# DNVT_box3r.net
KiCad netlist of a schematic drawn in EAGLE
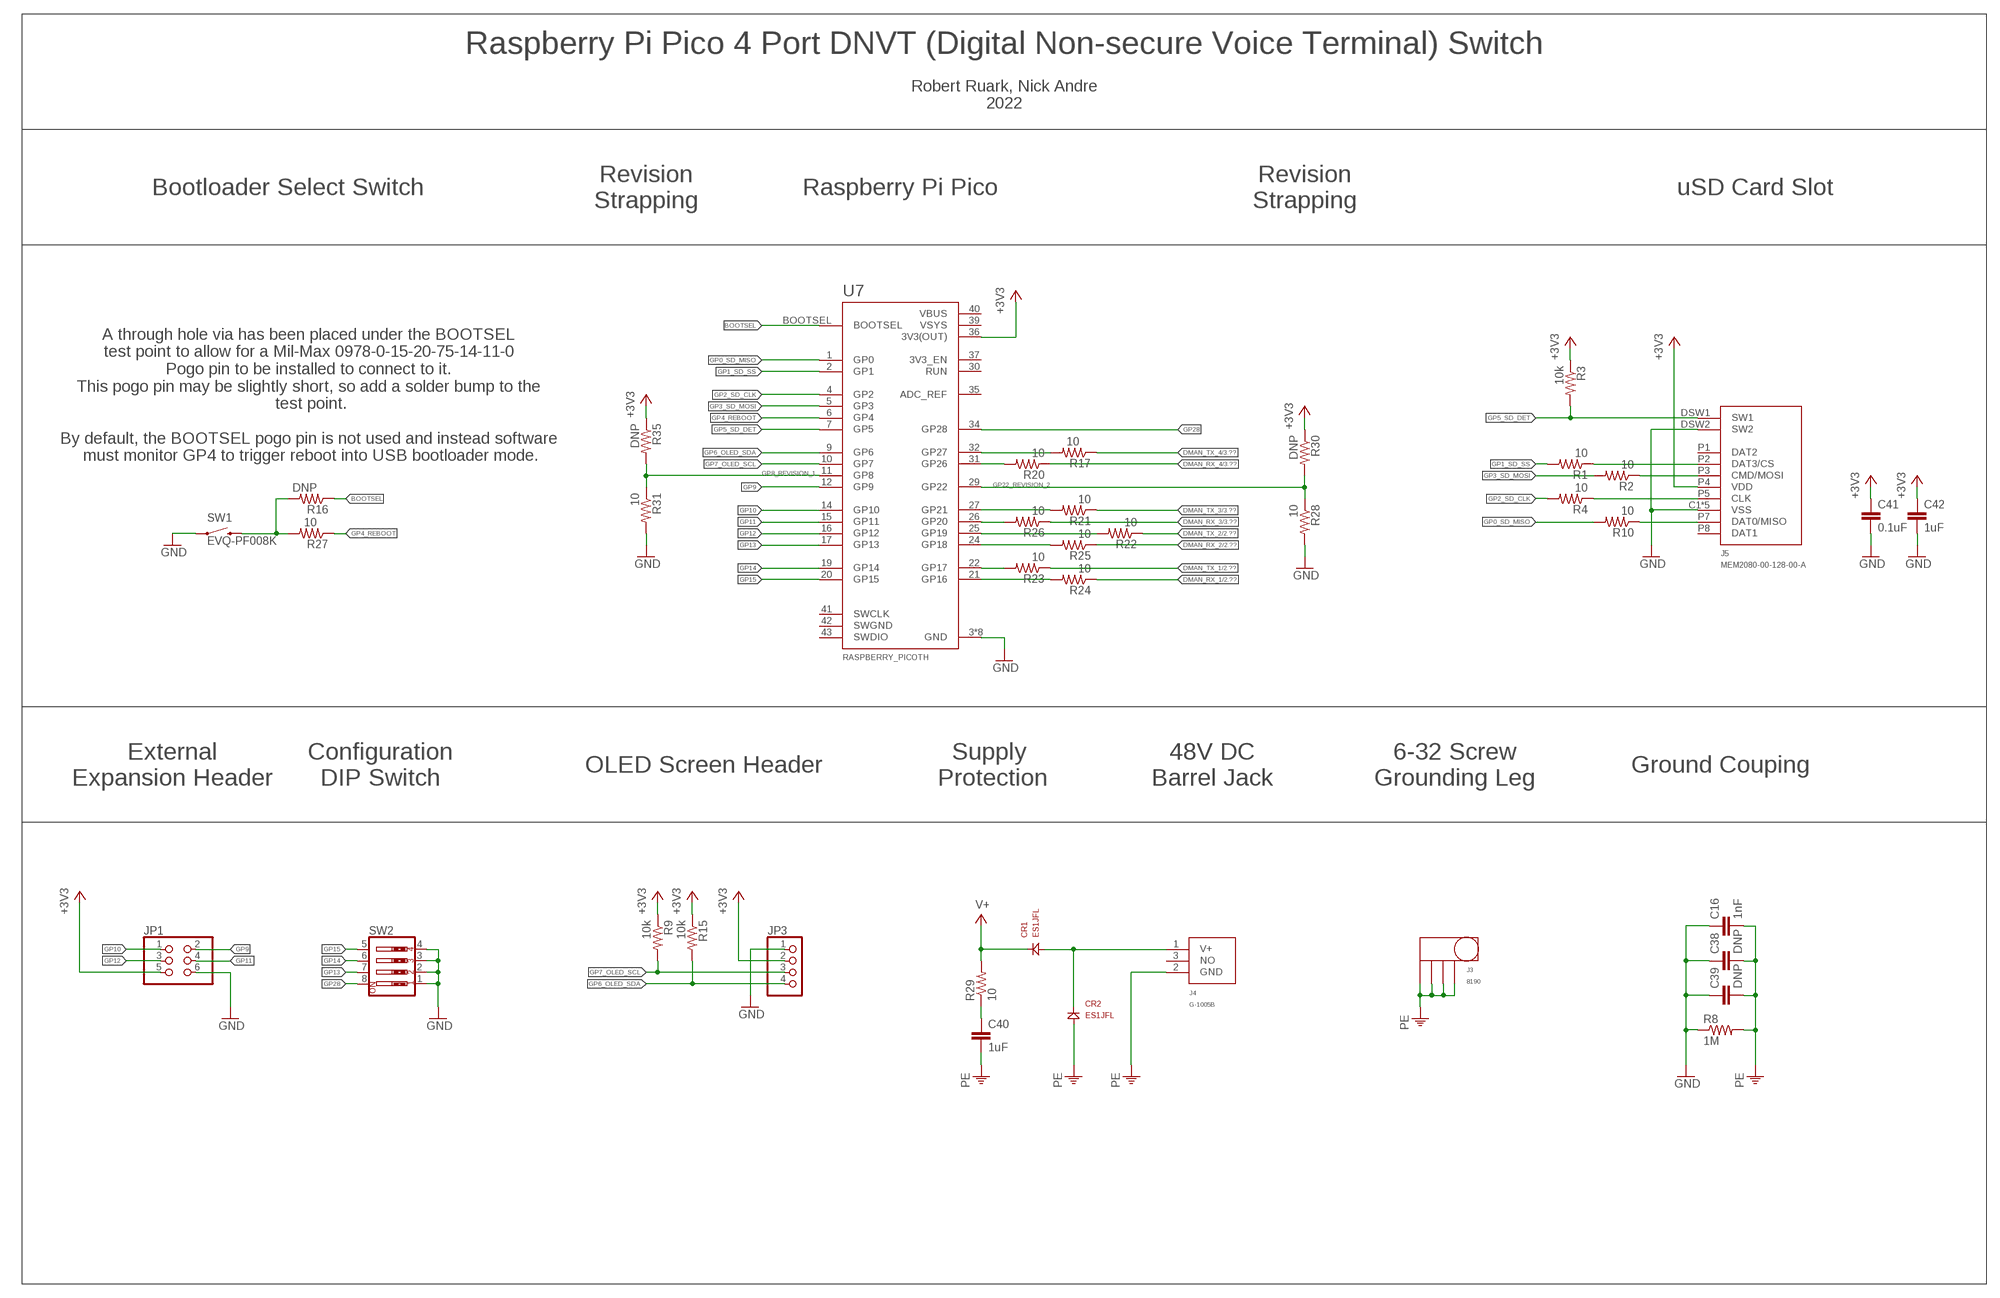
[diagram p0: schematic, sheet 1]
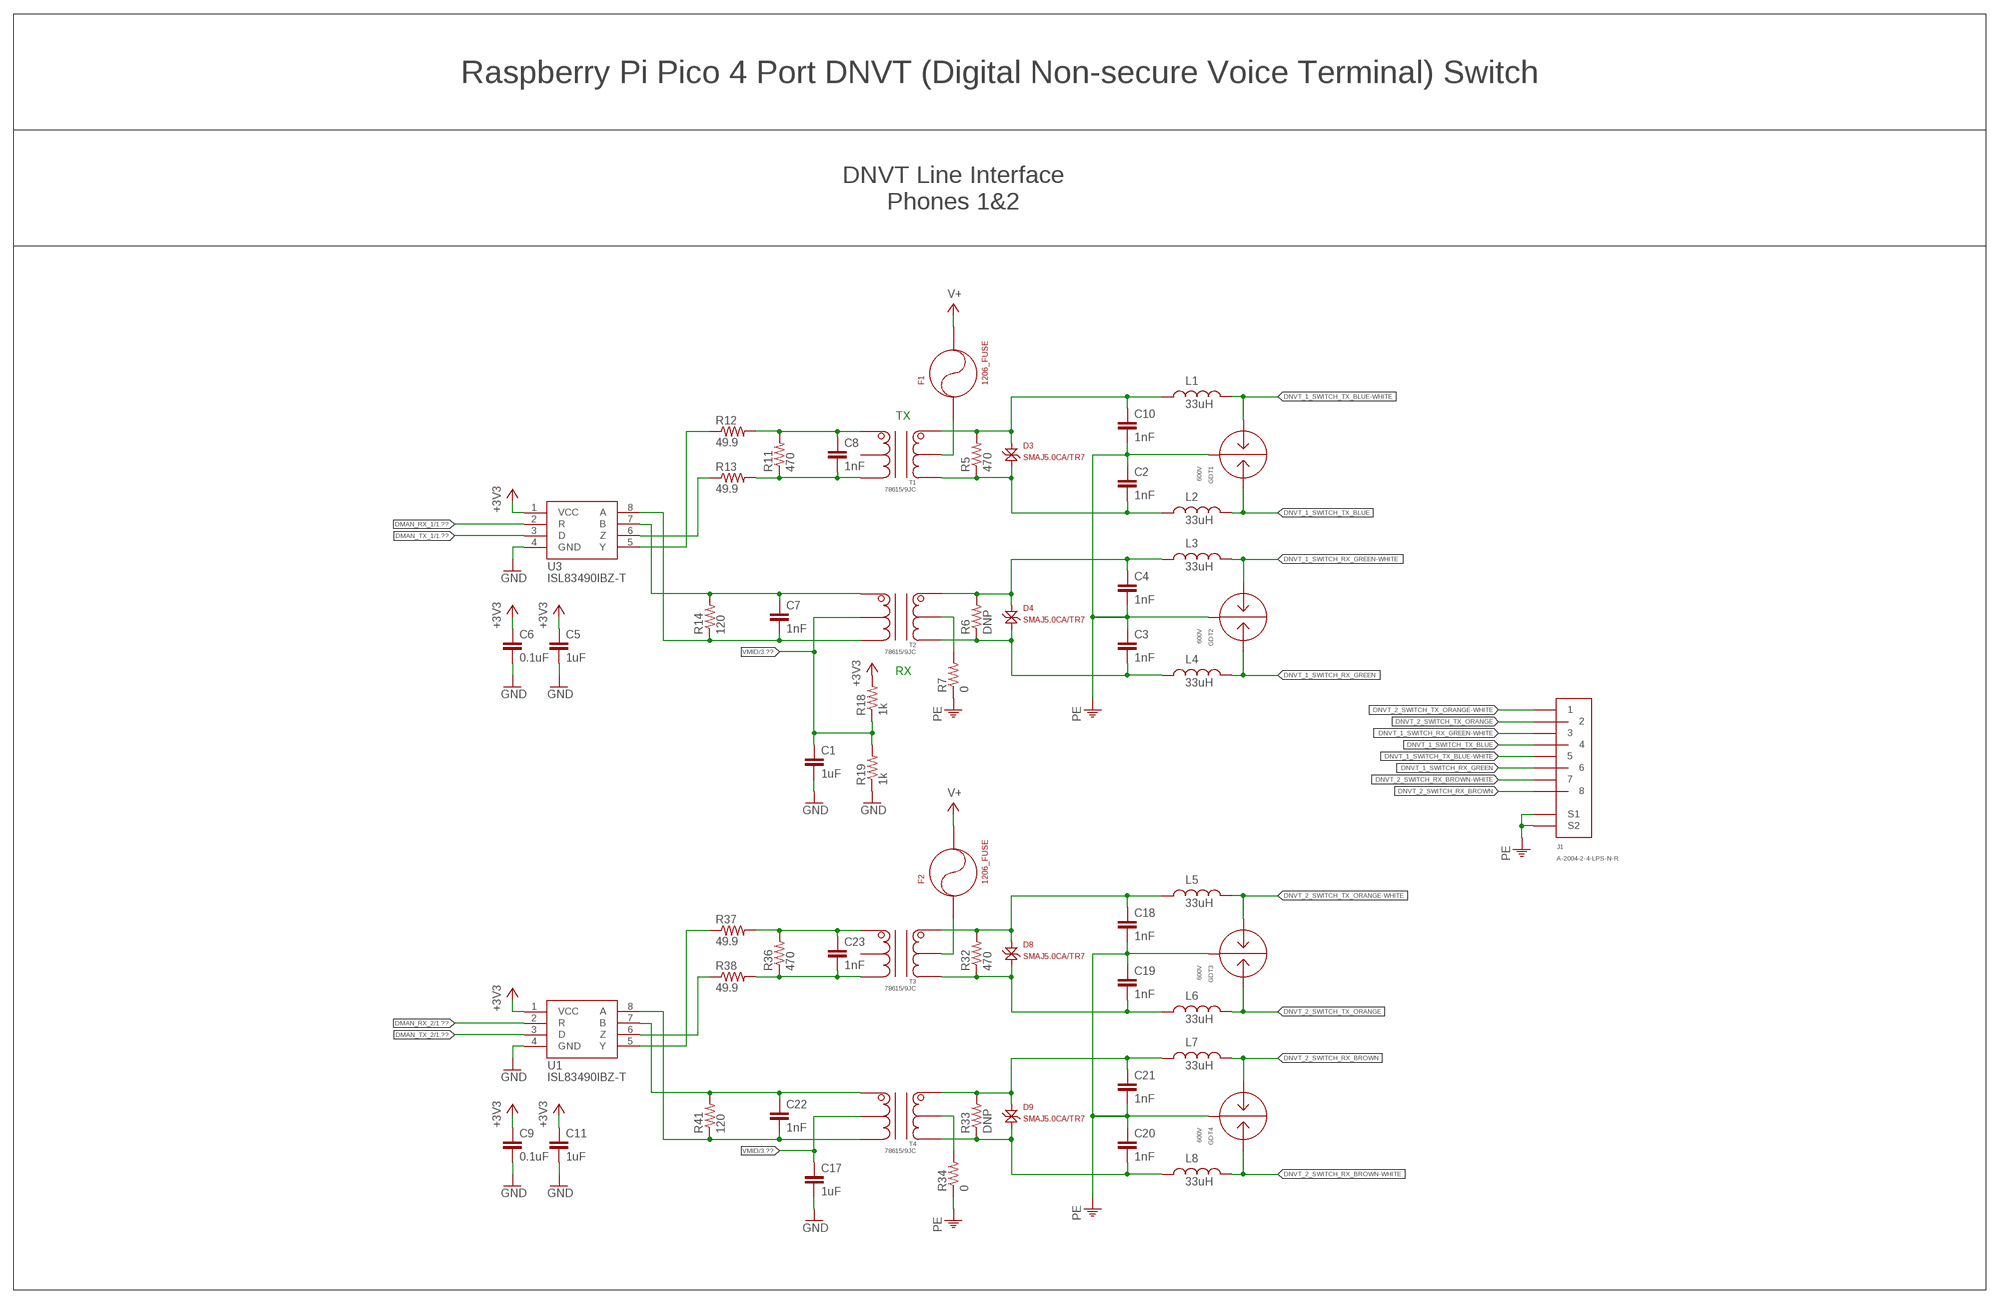
[diagram p1: schematic, sheet 2]
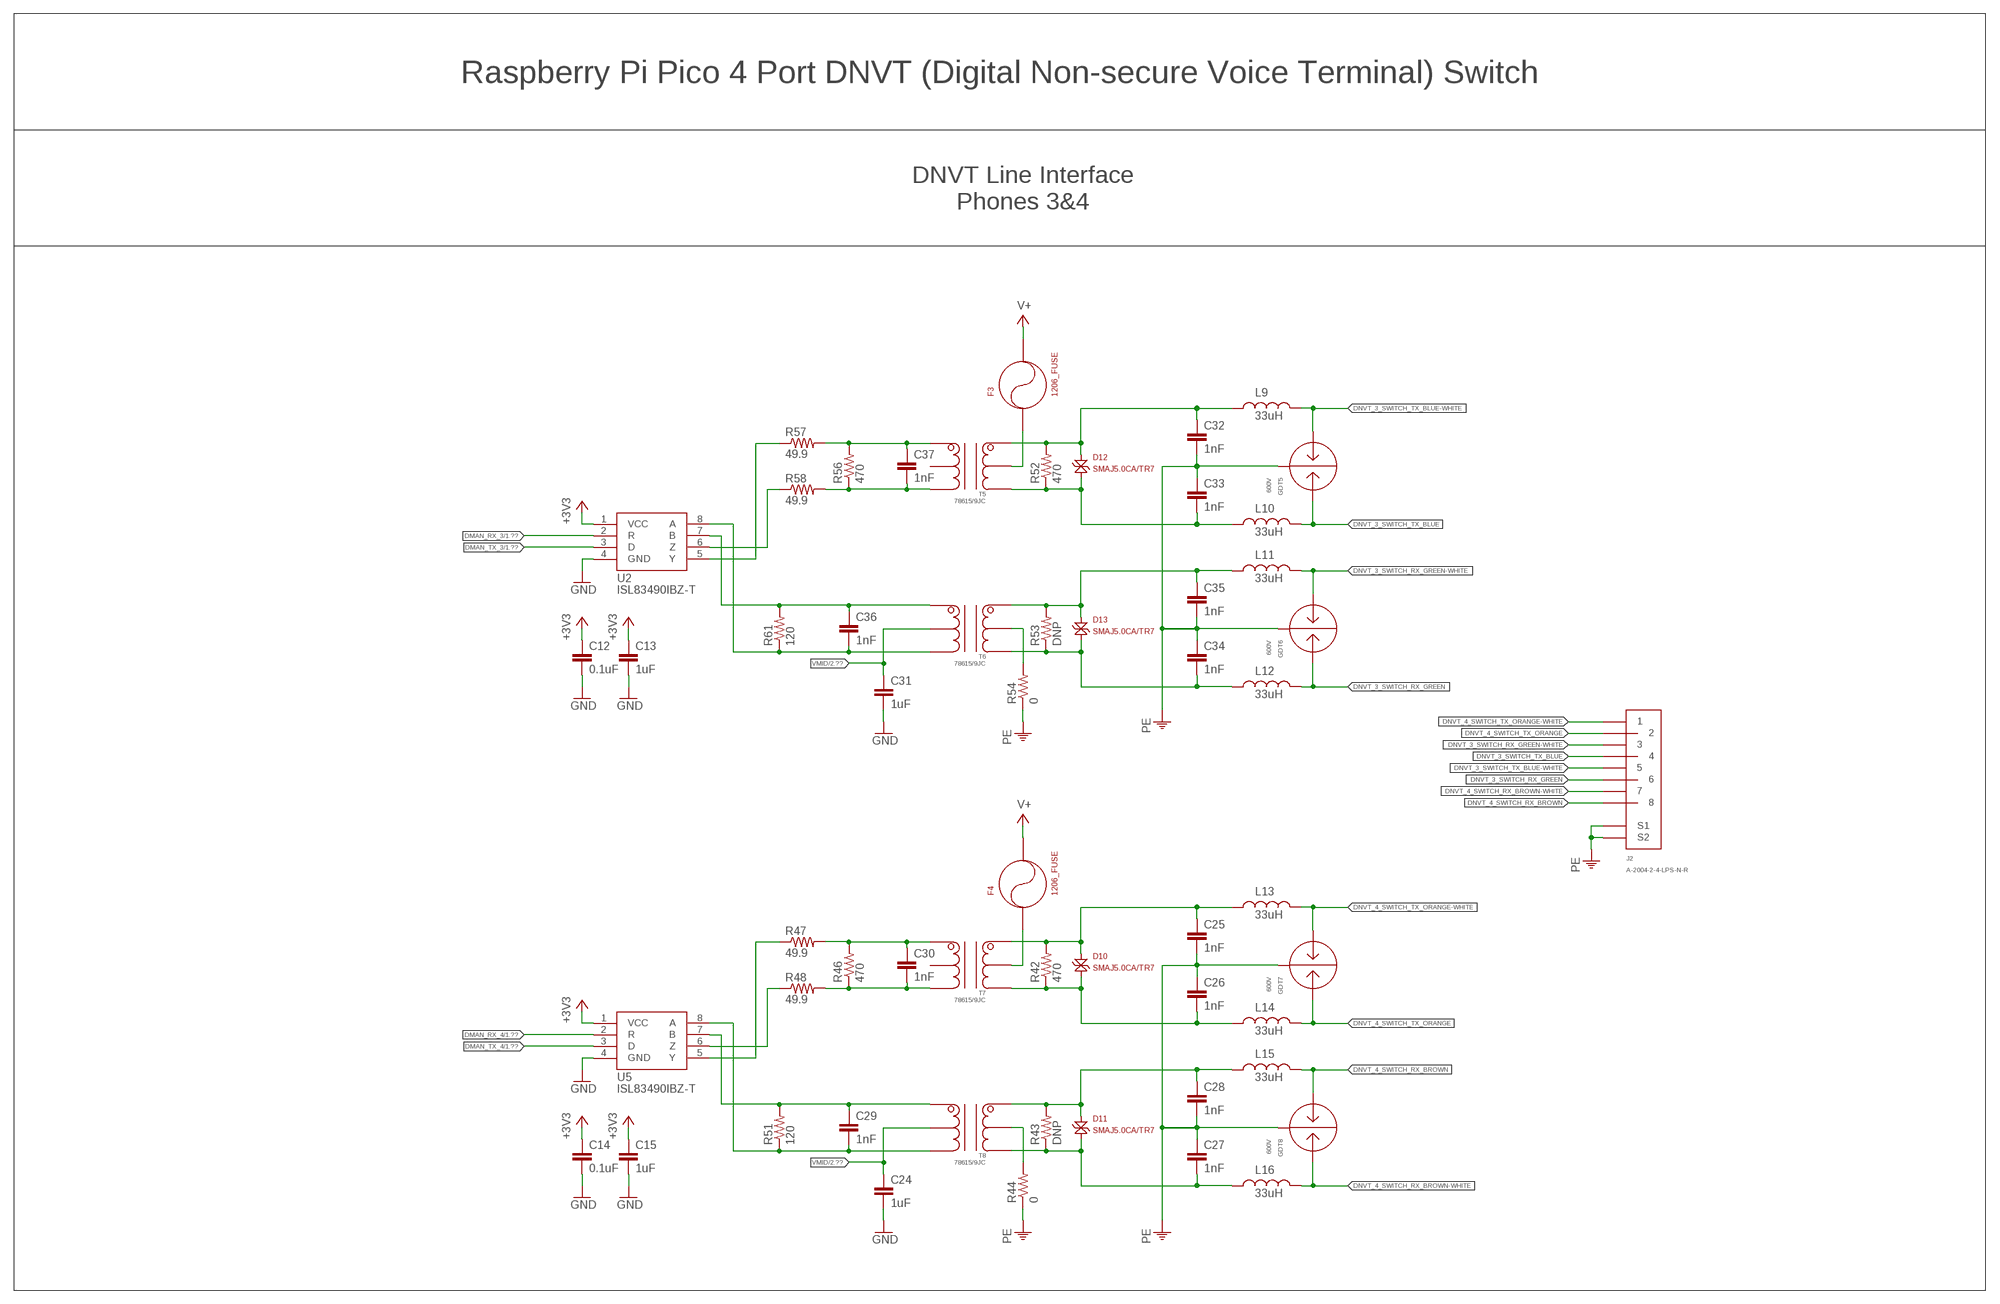
[diagram p2: schematic, sheet 3]

(export (version "E")
  (design (tool "Eeschema 10.0.6"))
  (components
    (comp (ref "C12")
      (value "0.1uF")
      (footprint "eagle-import:0603")
      (libsource (lib "eagle-import") (part "0603_CAPACITOR"))
    )
    (comp (ref "C13")
      (value "1uF")
      (footprint "eagle-import:0805")
      (libsource (lib "eagle-import") (part "0805_CAPACITOR"))
    )
    (comp (ref "C14")
      (value "0.1uF")
      (footprint "eagle-import:0603")
      (libsource (lib "eagle-import") (part "0603_CAPACITOR"))
    )
    (comp (ref "C15")
      (value "1uF")
      (footprint "eagle-import:0805")
      (libsource (lib "eagle-import") (part "0805_CAPACITOR"))
    )
    (comp (ref "C24")
      (value "1uF")
      (footprint "eagle-import:0805")
      (libsource (lib "eagle-import") (part "0805_CAPACITOR"))
    )
    (comp (ref "C25")
      (value "1nF")
      (footprint "eagle-import:0805")
      (libsource (lib "eagle-import") (part "0805_CAPACITOR"))
    )
    (comp (ref "C26")
      (value "1nF")
      (footprint "eagle-import:0805")
      (libsource (lib "eagle-import") (part "0805_CAPACITOR"))
    )
    (comp (ref "C27")
      (value "1nF")
      (footprint "eagle-import:0805")
      (libsource (lib "eagle-import") (part "0805_CAPACITOR"))
    )
    (comp (ref "C28")
      (value "1nF")
      (footprint "eagle-import:0805")
      (libsource (lib "eagle-import") (part "0805_CAPACITOR"))
    )
    (comp (ref "C29")
      (value "1nF")
      (footprint "eagle-import:0805")
      (libsource (lib "eagle-import") (part "0805_CAPACITOR"))
    )
    (comp (ref "C30")
      (value "1nF")
      (footprint "eagle-import:0805")
      (libsource (lib "eagle-import") (part "0805_CAPACITOR"))
    )
    (comp (ref "C31")
      (value "1uF")
      (footprint "eagle-import:0805")
      (libsource (lib "eagle-import") (part "0805_CAPACITOR"))
    )
    (comp (ref "C32")
      (value "1nF")
      (footprint "eagle-import:0805")
      (libsource (lib "eagle-import") (part "0805_CAPACITOR"))
    )
    (comp (ref "C33")
      (value "1nF")
      (footprint "eagle-import:0805")
      (libsource (lib "eagle-import") (part "0805_CAPACITOR"))
    )
    (comp (ref "C34")
      (value "1nF")
      (footprint "eagle-import:0805")
      (libsource (lib "eagle-import") (part "0805_CAPACITOR"))
    )
    (comp (ref "C35")
      (value "1nF")
      (footprint "eagle-import:0805")
      (libsource (lib "eagle-import") (part "0805_CAPACITOR"))
    )
    (comp (ref "C36")
      (value "1nF")
      (footprint "eagle-import:0805")
      (libsource (lib "eagle-import") (part "0805_CAPACITOR"))
    )
    (comp (ref "C37")
      (value "1nF")
      (footprint "eagle-import:0805")
      (libsource (lib "eagle-import") (part "0805_CAPACITOR"))
    )
    (comp (ref "D10")
      (value "SMAJ5.0CA/TR7")
      (footprint "eagle-import:DO-214AC_NO_POL")
      (libsource (lib "eagle-import") (part "SMAJ5.0CA/TR7"))
    )
    (comp (ref "D11")
      (value "SMAJ5.0CA/TR7")
      (footprint "eagle-import:DO-214AC_NO_POL")
      (libsource (lib "eagle-import") (part "SMAJ5.0CA/TR7"))
    )
    (comp (ref "D12")
      (value "SMAJ5.0CA/TR7")
      (footprint "eagle-import:DO-214AC_NO_POL")
      (libsource (lib "eagle-import") (part "SMAJ5.0CA/TR7"))
    )
    (comp (ref "D13")
      (value "SMAJ5.0CA/TR7")
      (footprint "eagle-import:DO-214AC_NO_POL")
      (libsource (lib "eagle-import") (part "SMAJ5.0CA/TR7"))
    )
    (comp (ref "F3")
      (value "1206_FUSE")
      (footprint "eagle-import:1206")
      (libsource (lib "eagle-import") (part "1206_FUSE"))
    )
    (comp (ref "F4")
      (value "1206_FUSE")
      (footprint "eagle-import:1206")
      (libsource (lib "eagle-import") (part "1206_FUSE"))
    )
    (comp (ref "GDT5")
      (value "600V")
      (footprint "eagle-import:2036_GDT")
      (fields (field (name "PARTNO") "2036-60-SM-RPLFCT-ND"))
      (libsource (lib "eagle-import") (part "2036-60-SM-RPLF"))
    )
    (comp (ref "GDT6")
      (value "600V")
      (footprint "eagle-import:2036_GDT")
      (fields (field (name "PARTNO") "2036-60-SM-RPLFCT-ND"))
      (libsource (lib "eagle-import") (part "2036-60-SM-RPLF"))
    )
    (comp (ref "GDT7")
      (value "600V")
      (footprint "eagle-import:2036_GDT")
      (fields (field (name "PARTNO") "2036-60-SM-RPLFCT-ND"))
      (libsource (lib "eagle-import") (part "2036-60-SM-RPLF"))
    )
    (comp (ref "GDT8")
      (value "600V")
      (footprint "eagle-import:2036_GDT")
      (fields (field (name "PARTNO") "2036-60-SM-RPLFCT-ND"))
      (libsource (lib "eagle-import") (part "2036-60-SM-RPLF"))
    )
    (comp (ref "J2")
      (value "A-2004-2-4-LPS-N-R")
      (footprint "eagle-import:A-2004-2-4-LPS-N-R")
      (fields (field (name "PARTNO") "AE10387-ND"))
      (libsource (lib "eagle-import") (part "A-2004-2-4-LPS-N-R"))
    )
    (comp (ref "L9")
      (value "33uH")
      (footprint "eagle-import:SDR0403")
      (fields (field (name "PARTNO") "SDR0403-330KLCT-ND"))
      (libsource (lib "eagle-import") (part "SDR0403-330KL"))
    )
    (comp (ref "L10")
      (value "33uH")
      (footprint "eagle-import:SDR0403")
      (fields (field (name "PARTNO") "SDR0403-330KLCT-ND"))
      (libsource (lib "eagle-import") (part "SDR0403-330KL"))
    )
    (comp (ref "L11")
      (value "33uH")
      (footprint "eagle-import:SDR0403")
      (fields (field (name "PARTNO") "SDR0403-330KLCT-ND"))
      (libsource (lib "eagle-import") (part "SDR0403-330KL"))
    )
    (comp (ref "L12")
      (value "33uH")
      (footprint "eagle-import:SDR0403")
      (fields (field (name "PARTNO") "SDR0403-330KLCT-ND"))
      (libsource (lib "eagle-import") (part "SDR0403-330KL"))
    )
    (comp (ref "L13")
      (value "33uH")
      (footprint "eagle-import:SDR0403")
      (fields (field (name "PARTNO") "SDR0403-330KLCT-ND"))
      (libsource (lib "eagle-import") (part "SDR0403-330KL"))
    )
    (comp (ref "L14")
      (value "33uH")
      (footprint "eagle-import:SDR0403")
      (fields (field (name "PARTNO") "SDR0403-330KLCT-ND"))
      (libsource (lib "eagle-import") (part "SDR0403-330KL"))
    )
    (comp (ref "L15")
      (value "33uH")
      (footprint "eagle-import:SDR0403")
      (fields (field (name "PARTNO") "SDR0403-330KLCT-ND"))
      (libsource (lib "eagle-import") (part "SDR0403-330KL"))
    )
    (comp (ref "L16")
      (value "33uH")
      (footprint "eagle-import:SDR0403")
      (fields (field (name "PARTNO") "SDR0403-330KLCT-ND"))
      (libsource (lib "eagle-import") (part "SDR0403-330KL"))
    )
    (comp (ref "R42")
      (value "470")
      (footprint "eagle-import:R0805")
      (libsource (lib "eagle-import") (part "R-US_R0805"))
    )
    (comp (ref "R43")
      (value "DNP")
      (footprint "eagle-import:R0805")
      (libsource (lib "eagle-import") (part "R-US_R0805"))
    )
    (comp (ref "R44")
      (value "0")
      (footprint "eagle-import:R0805")
      (libsource (lib "eagle-import") (part "R-US_R0805"))
    )
    (comp (ref "R46")
      (value "470")
      (footprint "eagle-import:R0805")
      (libsource (lib "eagle-import") (part "R-US_R0805"))
    )
    (comp (ref "R47")
      (value "49.9")
      (footprint "eagle-import:R0805")
      (libsource (lib "eagle-import") (part "R-US_R0805"))
    )
    (comp (ref "R48")
      (value "49.9")
      (footprint "eagle-import:R0805")
      (libsource (lib "eagle-import") (part "R-US_R0805"))
    )
    (comp (ref "R51")
      (value "120")
      (footprint "eagle-import:1206")
      (libsource (lib "eagle-import") (part "1206_RESISTOR"))
    )
    (comp (ref "R52")
      (value "470")
      (footprint "eagle-import:R0805")
      (libsource (lib "eagle-import") (part "R-US_R0805"))
    )
    (comp (ref "R53")
      (value "DNP")
      (footprint "eagle-import:R0805")
      (libsource (lib "eagle-import") (part "R-US_R0805"))
    )
    (comp (ref "R54")
      (value "0")
      (footprint "eagle-import:R0805")
      (libsource (lib "eagle-import") (part "R-US_R0805"))
    )
    (comp (ref "R56")
      (value "470")
      (footprint "eagle-import:R0805")
      (libsource (lib "eagle-import") (part "R-US_R0805"))
    )
    (comp (ref "R57")
      (value "49.9")
      (footprint "eagle-import:R0805")
      (libsource (lib "eagle-import") (part "R-US_R0805"))
    )
    (comp (ref "R58")
      (value "49.9")
      (footprint "eagle-import:R0805")
      (libsource (lib "eagle-import") (part "R-US_R0805"))
    )
    (comp (ref "R61")
      (value "120")
      (footprint "eagle-import:1206")
      (libsource (lib "eagle-import") (part "1206_RESISTOR"))
    )
    (comp (ref "T5")
      (value "78615/9JC")
      (footprint "eagle-import:786")
      (fields (field (name "PARTNO") "811-2423-ND"))
      (libsource (lib "eagle-import") (part "78615/9JC"))
    )
    (comp (ref "T6")
      (value "78615/9JC")
      (footprint "eagle-import:786")
      (fields (field (name "PARTNO") "811-2423-ND"))
      (libsource (lib "eagle-import") (part "78615/9JC"))
    )
    (comp (ref "T7")
      (value "78615/9JC")
      (footprint "eagle-import:786")
      (fields (field (name "PARTNO") "811-2423-ND"))
      (libsource (lib "eagle-import") (part "78615/9JC"))
    )
    (comp (ref "T8")
      (value "78615/9JC")
      (footprint "eagle-import:786")
      (fields (field (name "PARTNO") "811-2423-ND"))
      (libsource (lib "eagle-import") (part "78615/9JC"))
    )
    (comp (ref "U2")
      (value "ISL83490IBZ-T")
      (footprint "eagle-import:SOIC8")
      (fields (field (name "PARTNO") "ISL83490IBZ-TCT-ND"))
      (libsource (lib "eagle-import") (part "ISL83490IBZ-T"))
    )
    (comp (ref "U5")
      (value "ISL83490IBZ-T")
      (footprint "eagle-import:SOIC8")
      (fields (field (name "PARTNO") "ISL83490IBZ-TCT-ND"))
      (libsource (lib "eagle-import") (part "ISL83490IBZ-T"))
    )
    (comp (ref "C16")
      (value "1nF")
      (footprint "eagle-import:1206")
      (libsource (lib "eagle-import") (part "1206_CAPACITOR"))
    )
    (comp (ref "C38")
      (value "DNP")
      (footprint "eagle-import:1206")
      (libsource (lib "eagle-import") (part "1206_CAPACITOR"))
    )
    (comp (ref "C39")
      (value "DNP")
      (footprint "eagle-import:1206")
      (libsource (lib "eagle-import") (part "1206_CAPACITOR"))
    )
    (comp (ref "C40")
      (value "1uF")
      (footprint "eagle-import:1206")
      (libsource (lib "eagle-import") (part "1206_CAPACITOR"))
    )
    (comp (ref "C41")
      (value "0.1uF")
      (footprint "eagle-import:0603")
      (libsource (lib "eagle-import") (part "0603_CAPACITOR"))
    )
    (comp (ref "C42")
      (value "1uF")
      (footprint "eagle-import:0805")
      (libsource (lib "eagle-import") (part "0805_CAPACITOR"))
    )
    (comp (ref "CR1")
      (value "ES1JFL")
      (footprint "eagle-import:SOD123(AK)")
      (fields (field (name "PARTNO") "ES1JFLCT-ND"))
      (libsource (lib "eagle-import") (part "ES1JFL"))
    )
    (comp (ref "CR2")
      (value "ES1JFL")
      (footprint "eagle-import:SOD123(AK)")
      (fields (field (name "PARTNO") "ES1JFLCT-ND"))
      (libsource (lib "eagle-import") (part "ES1JFL"))
    )
    (comp (ref "J3")
      (value "8190")
      (footprint "eagle-import:7781")
      (fields (field (name "PARTNO") "36-8190-ND"))
      (libsource (lib "eagle-import") (part "8190"))
    )
    (comp (ref "J4")
      (value "G-1005B")
      (footprint "eagle-import:G-1005B")
      (fields (field (name "PARTNO") "1939-G-1005B-ND"))
      (libsource (lib "eagle-import") (part "G-1005B"))
    )
    (comp (ref "J5")
      (value "MEM2080-00-128-00-A")
      (footprint "eagle-import:MEM2080")
      (fields (field (name "PARTNO") "2073-MEM2080-00-128-00-ACT-ND"))
      (libsource (lib "eagle-import") (part "MEM2080-00-128-00-A"))
    )
    (comp (ref "JP1")
      (value "PINHD-2X3/90")
      (footprint "eagle-import:2X03_90")
      (libsource (lib "eagle-import") (part "PINHD-2X3/90"))
    )
    (comp (ref "JP3")
      (value "PINHD-1X4")
      (footprint "eagle-import:1X04")
      (libsource (lib "eagle-import") (part "PINHD-1X4"))
    )
    (comp (ref "R1")
      (value "10")
      (footprint "eagle-import:0603")
      (libsource (lib "eagle-import") (part "0603_RESISTOR"))
    )
    (comp (ref "R2")
      (value "10")
      (footprint "eagle-import:0603")
      (libsource (lib "eagle-import") (part "0603_RESISTOR"))
    )
    (comp (ref "R3")
      (value "10k")
      (footprint "eagle-import:0603")
      (libsource (lib "eagle-import") (part "0603_RESISTOR"))
    )
    (comp (ref "R4")
      (value "10")
      (footprint "eagle-import:0603")
      (libsource (lib "eagle-import") (part "0603_RESISTOR"))
    )
    (comp (ref "R8")
      (value "1M")
      (footprint "eagle-import:1206")
      (libsource (lib "eagle-import") (part "1206_RESISTOR"))
    )
    (comp (ref "R9")
      (value "10k")
      (footprint "eagle-import:0603")
      (libsource (lib "eagle-import") (part "0603_RESISTOR"))
    )
    (comp (ref "R10")
      (value "10")
      (footprint "eagle-import:0603")
      (libsource (lib "eagle-import") (part "0603_RESISTOR"))
    )
    (comp (ref "R15")
      (value "10k")
      (footprint "eagle-import:0603")
      (libsource (lib "eagle-import") (part "0603_RESISTOR"))
    )
    (comp (ref "R16")
      (value "DNP")
      (footprint "eagle-import:0603")
      (libsource (lib "eagle-import") (part "0603_RESISTOR"))
    )
    (comp (ref "R17")
      (value "10")
      (footprint "eagle-import:0603")
      (libsource (lib "eagle-import") (part "0603_RESISTOR"))
    )
    (comp (ref "R20")
      (value "10")
      (footprint "eagle-import:0603")
      (libsource (lib "eagle-import") (part "0603_RESISTOR"))
    )
    (comp (ref "R21")
      (value "10")
      (footprint "eagle-import:0603")
      (libsource (lib "eagle-import") (part "0603_RESISTOR"))
    )
    (comp (ref "R22")
      (value "10")
      (footprint "eagle-import:0603")
      (libsource (lib "eagle-import") (part "0603_RESISTOR"))
    )
    (comp (ref "R23")
      (value "10")
      (footprint "eagle-import:0603")
      (libsource (lib "eagle-import") (part "0603_RESISTOR"))
    )
    (comp (ref "R24")
      (value "10")
      (footprint "eagle-import:0603")
      (libsource (lib "eagle-import") (part "0603_RESISTOR"))
    )
    (comp (ref "R25")
      (value "10")
      (footprint "eagle-import:0603")
      (libsource (lib "eagle-import") (part "0603_RESISTOR"))
    )
    (comp (ref "R26")
      (value "10")
      (footprint "eagle-import:0603")
      (libsource (lib "eagle-import") (part "0603_RESISTOR"))
    )
    (comp (ref "R27")
      (value "10")
      (footprint "eagle-import:0603")
      (libsource (lib "eagle-import") (part "0603_RESISTOR"))
    )
    (comp (ref "R28")
      (value "10")
      (footprint "eagle-import:0603")
      (libsource (lib "eagle-import") (part "0603_RESISTOR"))
    )
    (comp (ref "R29")
      (value "10")
      (footprint "eagle-import:1206")
      (libsource (lib "eagle-import") (part "1206_RESISTOR"))
    )
    (comp (ref "R30")
      (value "DNP")
      (footprint "eagle-import:0603")
      (libsource (lib "eagle-import") (part "0603_RESISTOR"))
    )
    (comp (ref "R31")
      (value "10")
      (footprint "eagle-import:0603")
      (libsource (lib "eagle-import") (part "0603_RESISTOR"))
    )
    (comp (ref "R35")
      (value "DNP")
      (footprint "eagle-import:0603")
      (libsource (lib "eagle-import") (part "0603_RESISTOR"))
    )
    (comp (ref "SW1")
      (value "EVQ-PF008K")
      (footprint "eagle-import:EVQ-PF008K")
      (fields (field (name "PARTNO") "P10880S-ND"))
      (libsource (lib "eagle-import") (part "EVQ-PF008K"))
    )
    (comp (ref "SW2")
      (value "SW_DIP-4")
      (footprint "eagle-import:EDG-04")
      (libsource (lib "eagle-import") (part "SW_DIP-4"))
    )
    (comp (ref "U7")
      (value "RASPBERRY_PICOTH")
      (footprint "eagle-import:PICO-PKG-TH")
      (libsource (lib "eagle-import") (part "RASPBERRY_PICOTH"))
    )
    (comp (ref "C1")
      (value "1uF")
      (footprint "eagle-import:0805")
      (libsource (lib "eagle-import") (part "0805_CAPACITOR"))
    )
    (comp (ref "C2")
      (value "1nF")
      (footprint "eagle-import:0805")
      (libsource (lib "eagle-import") (part "0805_CAPACITOR"))
    )
    (comp (ref "C3")
      (value "1nF")
      (footprint "eagle-import:0805")
      (libsource (lib "eagle-import") (part "0805_CAPACITOR"))
    )
    (comp (ref "C4")
      (value "1nF")
      (footprint "eagle-import:0805")
      (libsource (lib "eagle-import") (part "0805_CAPACITOR"))
    )
    (comp (ref "C5")
      (value "1uF")
      (footprint "eagle-import:0805")
      (libsource (lib "eagle-import") (part "0805_CAPACITOR"))
    )
    (comp (ref "C6")
      (value "0.1uF")
      (footprint "eagle-import:0603")
      (libsource (lib "eagle-import") (part "0603_CAPACITOR"))
    )
    (comp (ref "C7")
      (value "1nF")
      (footprint "eagle-import:0805")
      (libsource (lib "eagle-import") (part "0805_CAPACITOR"))
    )
    (comp (ref "C8")
      (value "1nF")
      (footprint "eagle-import:0805")
      (libsource (lib "eagle-import") (part "0805_CAPACITOR"))
    )
    (comp (ref "C9")
      (value "0.1uF")
      (footprint "eagle-import:0603")
      (libsource (lib "eagle-import") (part "0603_CAPACITOR"))
    )
    (comp (ref "C10")
      (value "1nF")
      (footprint "eagle-import:0805")
      (libsource (lib "eagle-import") (part "0805_CAPACITOR"))
    )
    (comp (ref "C11")
      (value "1uF")
      (footprint "eagle-import:0805")
      (libsource (lib "eagle-import") (part "0805_CAPACITOR"))
    )
    (comp (ref "C17")
      (value "1uF")
      (footprint "eagle-import:0805")
      (libsource (lib "eagle-import") (part "0805_CAPACITOR"))
    )
    (comp (ref "C18")
      (value "1nF")
      (footprint "eagle-import:0805")
      (libsource (lib "eagle-import") (part "0805_CAPACITOR"))
    )
    (comp (ref "C19")
      (value "1nF")
      (footprint "eagle-import:0805")
      (libsource (lib "eagle-import") (part "0805_CAPACITOR"))
    )
    (comp (ref "C20")
      (value "1nF")
      (footprint "eagle-import:0805")
      (libsource (lib "eagle-import") (part "0805_CAPACITOR"))
    )
    (comp (ref "C21")
      (value "1nF")
      (footprint "eagle-import:0805")
      (libsource (lib "eagle-import") (part "0805_CAPACITOR"))
    )
    (comp (ref "C22")
      (value "1nF")
      (footprint "eagle-import:0805")
      (libsource (lib "eagle-import") (part "0805_CAPACITOR"))
    )
    (comp (ref "C23")
      (value "1nF")
      (footprint "eagle-import:0805")
      (libsource (lib "eagle-import") (part "0805_CAPACITOR"))
    )
    (comp (ref "D3")
      (value "SMAJ5.0CA/TR7")
      (footprint "eagle-import:DO-214AC_NO_POL")
      (libsource (lib "eagle-import") (part "SMAJ5.0CA/TR7"))
    )
    (comp (ref "D4")
      (value "SMAJ5.0CA/TR7")
      (footprint "eagle-import:DO-214AC_NO_POL")
      (libsource (lib "eagle-import") (part "SMAJ5.0CA/TR7"))
    )
    (comp (ref "D8")
      (value "SMAJ5.0CA/TR7")
      (footprint "eagle-import:DO-214AC_NO_POL")
      (libsource (lib "eagle-import") (part "SMAJ5.0CA/TR7"))
    )
    (comp (ref "D9")
      (value "SMAJ5.0CA/TR7")
      (footprint "eagle-import:DO-214AC_NO_POL")
      (libsource (lib "eagle-import") (part "SMAJ5.0CA/TR7"))
    )
    (comp (ref "F1")
      (value "1206_FUSE")
      (footprint "eagle-import:1206")
      (libsource (lib "eagle-import") (part "1206_FUSE"))
    )
    (comp (ref "F2")
      (value "1206_FUSE")
      (footprint "eagle-import:1206")
      (libsource (lib "eagle-import") (part "1206_FUSE"))
    )
    (comp (ref "GDT1")
      (value "600V")
      (footprint "eagle-import:2036_GDT")
      (fields (field (name "PARTNO") "2036-60-SM-RPLFCT-ND"))
      (libsource (lib "eagle-import") (part "2036-60-SM-RPLF"))
    )
    (comp (ref "GDT2")
      (value "600V")
      (footprint "eagle-import:2036_GDT")
      (fields (field (name "PARTNO") "2036-60-SM-RPLFCT-ND"))
      (libsource (lib "eagle-import") (part "2036-60-SM-RPLF"))
    )
    (comp (ref "GDT3")
      (value "600V")
      (footprint "eagle-import:2036_GDT")
      (fields (field (name "PARTNO") "2036-60-SM-RPLFCT-ND"))
      (libsource (lib "eagle-import") (part "2036-60-SM-RPLF"))
    )
    (comp (ref "GDT4")
      (value "600V")
      (footprint "eagle-import:2036_GDT")
      (fields (field (name "PARTNO") "2036-60-SM-RPLFCT-ND"))
      (libsource (lib "eagle-import") (part "2036-60-SM-RPLF"))
    )
    (comp (ref "J1")
      (value "A-2004-2-4-LPS-N-R")
      (footprint "eagle-import:A-2004-2-4-LPS-N-R")
      (fields (field (name "PARTNO") "AE10387-ND"))
      (libsource (lib "eagle-import") (part "A-2004-2-4-LPS-N-R"))
    )
    (comp (ref "L1")
      (value "33uH")
      (footprint "eagle-import:SDR0403")
      (fields (field (name "PARTNO") "SDR0403-330KLCT-ND"))
      (libsource (lib "eagle-import") (part "SDR0403-330KL"))
    )
    (comp (ref "L2")
      (value "33uH")
      (footprint "eagle-import:SDR0403")
      (fields (field (name "PARTNO") "SDR0403-330KLCT-ND"))
      (libsource (lib "eagle-import") (part "SDR0403-330KL"))
    )
    (comp (ref "L3")
      (value "33uH")
      (footprint "eagle-import:SDR0403")
      (fields (field (name "PARTNO") "SDR0403-330KLCT-ND"))
      (libsource (lib "eagle-import") (part "SDR0403-330KL"))
    )
    (comp (ref "L4")
      (value "33uH")
      (footprint "eagle-import:SDR0403")
      (fields (field (name "PARTNO") "SDR0403-330KLCT-ND"))
      (libsource (lib "eagle-import") (part "SDR0403-330KL"))
    )
    (comp (ref "L5")
      (value "33uH")
      (footprint "eagle-import:SDR0403")
      (fields (field (name "PARTNO") "SDR0403-330KLCT-ND"))
      (libsource (lib "eagle-import") (part "SDR0403-330KL"))
    )
    (comp (ref "L6")
      (value "33uH")
      (footprint "eagle-import:SDR0403")
      (fields (field (name "PARTNO") "SDR0403-330KLCT-ND"))
      (libsource (lib "eagle-import") (part "SDR0403-330KL"))
    )
    (comp (ref "L7")
      (value "33uH")
      (footprint "eagle-import:SDR0403")
      (fields (field (name "PARTNO") "SDR0403-330KLCT-ND"))
      (libsource (lib "eagle-import") (part "SDR0403-330KL"))
    )
    (comp (ref "L8")
      (value "33uH")
      (footprint "eagle-import:SDR0403")
      (fields (field (name "PARTNO") "SDR0403-330KLCT-ND"))
      (libsource (lib "eagle-import") (part "SDR0403-330KL"))
    )
    (comp (ref "R5")
      (value "470")
      (footprint "eagle-import:R0805")
      (libsource (lib "eagle-import") (part "R-US_R0805"))
    )
    (comp (ref "R6")
      (value "DNP")
      (footprint "eagle-import:R0805")
      (libsource (lib "eagle-import") (part "R-US_R0805"))
    )
    (comp (ref "R7")
      (value "0")
      (footprint "eagle-import:R0805")
      (libsource (lib "eagle-import") (part "R-US_R0805"))
    )
    (comp (ref "R11")
      (value "470")
      (footprint "eagle-import:R0805")
      (libsource (lib "eagle-import") (part "R-US_R0805"))
    )
    (comp (ref "R12")
      (value "49.9")
      (footprint "eagle-import:R0805")
      (libsource (lib "eagle-import") (part "R-US_R0805"))
    )
    (comp (ref "R13")
      (value "49.9")
      (footprint "eagle-import:R0805")
      (libsource (lib "eagle-import") (part "R-US_R0805"))
    )
    (comp (ref "R14")
      (value "120")
      (footprint "eagle-import:1206")
      (libsource (lib "eagle-import") (part "1206_RESISTOR"))
    )
    (comp (ref "R18")
      (value "1k")
      (footprint "eagle-import:0603")
      (libsource (lib "eagle-import") (part "0603_RESISTOR"))
    )
    (comp (ref "R19")
      (value "1k")
      (footprint "eagle-import:0603")
      (libsource (lib "eagle-import") (part "0603_RESISTOR"))
    )
    (comp (ref "R32")
      (value "470")
      (footprint "eagle-import:R0805")
      (libsource (lib "eagle-import") (part "R-US_R0805"))
    )
    (comp (ref "R33")
      (value "DNP")
      (footprint "eagle-import:R0805")
      (libsource (lib "eagle-import") (part "R-US_R0805"))
    )
    (comp (ref "R34")
      (value "0")
      (footprint "eagle-import:R0805")
      (libsource (lib "eagle-import") (part "R-US_R0805"))
    )
    (comp (ref "R36")
      (value "470")
      (footprint "eagle-import:R0805")
      (libsource (lib "eagle-import") (part "R-US_R0805"))
    )
    (comp (ref "R37")
      (value "49.9")
      (footprint "eagle-import:R0805")
      (libsource (lib "eagle-import") (part "R-US_R0805"))
    )
    (comp (ref "R38")
      (value "49.9")
      (footprint "eagle-import:R0805")
      (libsource (lib "eagle-import") (part "R-US_R0805"))
    )
    (comp (ref "R41")
      (value "120")
      (footprint "eagle-import:1206")
      (libsource (lib "eagle-import") (part "1206_RESISTOR"))
    )
    (comp (ref "T1")
      (value "78615/9JC")
      (footprint "eagle-import:786")
      (fields (field (name "PARTNO") "811-2423-ND"))
      (libsource (lib "eagle-import") (part "78615/9JC"))
    )
    (comp (ref "T2")
      (value "78615/9JC")
      (footprint "eagle-import:786")
      (fields (field (name "PARTNO") "811-2423-ND"))
      (libsource (lib "eagle-import") (part "78615/9JC"))
    )
    (comp (ref "T3")
      (value "78615/9JC")
      (footprint "eagle-import:786")
      (fields (field (name "PARTNO") "811-2423-ND"))
      (libsource (lib "eagle-import") (part "78615/9JC"))
    )
    (comp (ref "T4")
      (value "78615/9JC")
      (footprint "eagle-import:786")
      (fields (field (name "PARTNO") "811-2423-ND"))
      (libsource (lib "eagle-import") (part "78615/9JC"))
    )
    (comp (ref "U1")
      (value "ISL83490IBZ-T")
      (footprint "eagle-import:SOIC8")
      (fields (field (name "PARTNO") "ISL83490IBZ-TCT-ND"))
      (libsource (lib "eagle-import") (part "ISL83490IBZ-T"))
    )
    (comp (ref "U3")
      (value "ISL83490IBZ-T")
      (footprint "eagle-import:SOIC8")
      (fields (field (name "PARTNO") "ISL83490IBZ-TCT-ND"))
      (libsource (lib "eagle-import") (part "ISL83490IBZ-T"))
    )
  )
  (nets
    (net (code "1") (name "+3V3") (class "Default")
      (node (ref "C11") (pin "1") (pinfunction "1_1") (pintype "passive"))
      (node (ref "C12") (pin "1") (pinfunction "1_1") (pintype "passive"))
      (node (ref "C13") (pin "1") (pinfunction "1_1") (pintype "passive"))
      (node (ref "C14") (pin "1") (pinfunction "1_1") (pintype "passive"))
      (node (ref "C15") (pin "1") (pinfunction "1_1") (pintype "passive"))
      (node (ref "C41") (pin "1") (pinfunction "1_1") (pintype "passive"))
      (node (ref "C42") (pin "1") (pinfunction "1_1") (pintype "passive"))
      (node (ref "C5") (pin "1") (pinfunction "1_1") (pintype "passive"))
      (node (ref "C6") (pin "1") (pinfunction "1_1") (pintype "passive"))
      (node (ref "C9") (pin "1") (pinfunction "1_1") (pintype "passive"))
      (node (ref "J5") (pin "P4") (pinfunction "VDD_P4") (pintype "bidirectional"))
      (node (ref "JP1") (pin "5") (pinfunction "5_5") (pintype "passive"))
      (node (ref "JP3") (pin "2") (pinfunction "2_2") (pintype "passive"))
      (node (ref "R15") (pin "1") (pinfunction "1_1") (pintype "passive"))
      (node (ref "R18") (pin "2") (pinfunction "2_2") (pintype "passive"))
      (node (ref "R3") (pin "1") (pinfunction "1_1") (pintype "passive"))
      (node (ref "R30") (pin "1") (pinfunction "1_1") (pintype "passive"))
      (node (ref "R35") (pin "1") (pinfunction "1_1") (pintype "passive"))
      (node (ref "R9") (pin "1") (pinfunction "1_1") (pintype "passive"))
      (node (ref "U1") (pin "1") (pinfunction "VCC_1") (pintype "bidirectional"))
      (node (ref "U2") (pin "1") (pinfunction "VCC_1") (pintype "bidirectional"))
      (node (ref "U3") (pin "1") (pinfunction "VCC_1") (pintype "bidirectional"))
      (node (ref "U5") (pin "1") (pinfunction "VCC_1") (pintype "bidirectional"))
      (node (ref "U7") (pin "36") (pinfunction "3V3(OUT)_36") (pintype "power_in"))
    )
    (net (code "2") (name "BOOTSEL") (class "Default")
      (node (ref "R16") (pin "1") (pinfunction "1_1") (pintype "passive"))
      (node (ref "U7") (pin "BOOTSEL") (pinfunction "BOOTSEL_BOOTSEL") (pintype "bidirectional"))
    )
    (net (code "3") (name "DMAN_RX_1") (class "Default")
      (node (ref "R24") (pin "1") (pinfunction "1_1") (pintype "passive"))
      (node (ref "U3") (pin "2") (pinfunction "R_2") (pintype "bidirectional"))
    )
    (net (code "4") (name "DMAN_RX_2") (class "Default")
      (node (ref "R25") (pin "1") (pinfunction "1_1") (pintype "passive"))
      (node (ref "U1") (pin "2") (pinfunction "R_2") (pintype "bidirectional"))
    )
    (net (code "5") (name "DMAN_RX_3") (class "Default")
      (node (ref "R26") (pin "1") (pinfunction "1_1") (pintype "passive"))
      (node (ref "U2") (pin "2") (pinfunction "R_2") (pintype "bidirectional"))
    )
    (net (code "6") (name "DMAN_RX_4") (class "Default")
      (node (ref "R20") (pin "1") (pinfunction "1_1") (pintype "passive"))
      (node (ref "U5") (pin "2") (pinfunction "R_2") (pintype "bidirectional"))
    )
    (net (code "7") (name "DMAN_TX_1") (class "Default")
      (node (ref "R23") (pin "1") (pinfunction "1_1") (pintype "passive"))
      (node (ref "U3") (pin "3") (pinfunction "D_3") (pintype "bidirectional"))
    )
    (net (code "8") (name "DMAN_TX_2") (class "Default")
      (node (ref "R22") (pin "1") (pinfunction "1_1") (pintype "passive"))
      (node (ref "U1") (pin "3") (pinfunction "D_3") (pintype "bidirectional"))
    )
    (net (code "9") (name "DMAN_TX_3") (class "Default")
      (node (ref "R21") (pin "1") (pinfunction "1_1") (pintype "passive"))
      (node (ref "U2") (pin "3") (pinfunction "D_3") (pintype "bidirectional"))
    )
    (net (code "10") (name "DMAN_TX_4") (class "Default")
      (node (ref "R17") (pin "1") (pinfunction "1_1") (pintype "passive"))
      (node (ref "U5") (pin "3") (pinfunction "D_3") (pintype "bidirectional"))
    )
    (net (code "11") (name "DNVT_1_SWITCH_RX_GREEN") (class "Default")
      (node (ref "GDT2") (pin "L2") (pinfunction "L2_L2") (pintype "bidirectional"))
      (node (ref "J1") (pin "6") (pinfunction "6_6") (pintype "bidirectional"))
      (node (ref "L4") (pin "2") (pinfunction "P$2_2") (pintype "bidirectional"))
    )
    (net (code "12") (name "DNVT_1_SWITCH_RX_GREEN-WHITE") (class "Default")
      (node (ref "GDT2") (pin "L1") (pinfunction "L1_L1") (pintype "bidirectional"))
      (node (ref "J1") (pin "3") (pinfunction "3_3") (pintype "bidirectional"))
      (node (ref "L3") (pin "2") (pinfunction "P$2_2") (pintype "bidirectional"))
    )
    (net (code "13") (name "DNVT_1_SWITCH_TX_BLUE") (class "Default")
      (node (ref "GDT1") (pin "L2") (pinfunction "L2_L2") (pintype "bidirectional"))
      (node (ref "J1") (pin "4") (pinfunction "4_4") (pintype "bidirectional"))
      (node (ref "L2") (pin "2") (pinfunction "P$2_2") (pintype "bidirectional"))
    )
    (net (code "14") (name "DNVT_1_SWITCH_TX_BLUE-WHITE") (class "Default")
      (node (ref "GDT1") (pin "L1") (pinfunction "L1_L1") (pintype "bidirectional"))
      (node (ref "J1") (pin "5") (pinfunction "5_5") (pintype "bidirectional"))
      (node (ref "L1") (pin "2") (pinfunction "P$2_2") (pintype "bidirectional"))
    )
    (net (code "15") (name "DNVT_2_SWITCH_RX_BROWN") (class "Default")
      (node (ref "GDT4") (pin "L1") (pinfunction "L1_L1") (pintype "bidirectional"))
      (node (ref "J1") (pin "8") (pinfunction "8_8") (pintype "bidirectional"))
      (node (ref "L7") (pin "2") (pinfunction "P$2_2") (pintype "bidirectional"))
    )
    (net (code "16") (name "DNVT_2_SWITCH_RX_BROWN-WHITE") (class "Default")
      (node (ref "GDT4") (pin "L2") (pinfunction "L2_L2") (pintype "bidirectional"))
      (node (ref "J1") (pin "7") (pinfunction "7_7") (pintype "bidirectional"))
      (node (ref "L8") (pin "2") (pinfunction "P$2_2") (pintype "bidirectional"))
    )
    (net (code "17") (name "DNVT_2_SWITCH_TX_ORANGE") (class "Default")
      (node (ref "GDT3") (pin "L2") (pinfunction "L2_L2") (pintype "bidirectional"))
      (node (ref "J1") (pin "2") (pinfunction "2_2") (pintype "bidirectional"))
      (node (ref "L6") (pin "2") (pinfunction "P$2_2") (pintype "bidirectional"))
    )
    (net (code "18") (name "DNVT_2_SWITCH_TX_ORANGE-WHITE") (class "Default")
      (node (ref "GDT3") (pin "L1") (pinfunction "L1_L1") (pintype "bidirectional"))
      (node (ref "J1") (pin "1") (pinfunction "1_1") (pintype "bidirectional"))
      (node (ref "L5") (pin "2") (pinfunction "P$2_2") (pintype "bidirectional"))
    )
    (net (code "19") (name "DNVT_3_SWITCH_RX_GREEN") (class "Default")
      (node (ref "GDT6") (pin "L2") (pinfunction "L2_L2") (pintype "bidirectional"))
      (node (ref "J2") (pin "6") (pinfunction "6_6") (pintype "bidirectional"))
      (node (ref "L12") (pin "2") (pinfunction "P$2_2") (pintype "bidirectional"))
    )
    (net (code "20") (name "DNVT_3_SWITCH_RX_GREEN-WHITE") (class "Default")
      (node (ref "GDT6") (pin "L1") (pinfunction "L1_L1") (pintype "bidirectional"))
      (node (ref "J2") (pin "3") (pinfunction "3_3") (pintype "bidirectional"))
      (node (ref "L11") (pin "2") (pinfunction "P$2_2") (pintype "bidirectional"))
    )
    (net (code "21") (name "DNVT_3_SWITCH_TX_BLUE") (class "Default")
      (node (ref "GDT5") (pin "L2") (pinfunction "L2_L2") (pintype "bidirectional"))
      (node (ref "J2") (pin "4") (pinfunction "4_4") (pintype "bidirectional"))
      (node (ref "L10") (pin "2") (pinfunction "P$2_2") (pintype "bidirectional"))
    )
    (net (code "22") (name "DNVT_3_SWITCH_TX_BLUE-WHITE") (class "Default")
      (node (ref "GDT5") (pin "L1") (pinfunction "L1_L1") (pintype "bidirectional"))
      (node (ref "J2") (pin "5") (pinfunction "5_5") (pintype "bidirectional"))
      (node (ref "L9") (pin "2") (pinfunction "P$2_2") (pintype "bidirectional"))
    )
    (net (code "23") (name "DNVT_4_SWITCH_RX_BROWN") (class "Default")
      (node (ref "GDT8") (pin "L1") (pinfunction "L1_L1") (pintype "bidirectional"))
      (node (ref "J2") (pin "8") (pinfunction "8_8") (pintype "bidirectional"))
      (node (ref "L15") (pin "2") (pinfunction "P$2_2") (pintype "bidirectional"))
    )
    (net (code "24") (name "DNVT_4_SWITCH_RX_BROWN-WHITE") (class "Default")
      (node (ref "GDT8") (pin "L2") (pinfunction "L2_L2") (pintype "bidirectional"))
      (node (ref "J2") (pin "7") (pinfunction "7_7") (pintype "bidirectional"))
      (node (ref "L16") (pin "2") (pinfunction "P$2_2") (pintype "bidirectional"))
    )
    (net (code "25") (name "DNVT_4_SWITCH_TX_ORANGE") (class "Default")
      (node (ref "GDT7") (pin "L2") (pinfunction "L2_L2") (pintype "bidirectional"))
      (node (ref "J2") (pin "2") (pinfunction "2_2") (pintype "bidirectional"))
      (node (ref "L14") (pin "2") (pinfunction "P$2_2") (pintype "bidirectional"))
    )
    (net (code "26") (name "DNVT_4_SWITCH_TX_ORANGE-WHITE") (class "Default")
      (node (ref "GDT7") (pin "L1") (pinfunction "L1_L1") (pintype "bidirectional"))
      (node (ref "J2") (pin "1") (pinfunction "1_1") (pintype "bidirectional"))
      (node (ref "L13") (pin "2") (pinfunction "P$2_2") (pintype "bidirectional"))
    )
    (net (code "27") (name "GND") (class "Default")
      (node (ref "C1") (pin "2") (pinfunction "2_2") (pintype "passive"))
      (node (ref "C11") (pin "2") (pinfunction "2_2") (pintype "passive"))
      (node (ref "C12") (pin "2") (pinfunction "2_2") (pintype "passive"))
      (node (ref "C13") (pin "2") (pinfunction "2_2") (pintype "passive"))
      (node (ref "C14") (pin "2") (pinfunction "2_2") (pintype "passive"))
      (node (ref "C15") (pin "2") (pinfunction "2_2") (pintype "passive"))
      (node (ref "C16") (pin "1") (pinfunction "1_1") (pintype "passive"))
      (node (ref "C17") (pin "2") (pinfunction "2_2") (pintype "passive"))
      (node (ref "C24") (pin "2") (pinfunction "2_2") (pintype "passive"))
      (node (ref "C31") (pin "2") (pinfunction "2_2") (pintype "passive"))
      (node (ref "C38") (pin "1") (pinfunction "1_1") (pintype "passive"))
      (node (ref "C39") (pin "1") (pinfunction "1_1") (pintype "passive"))
      (node (ref "C41") (pin "2") (pinfunction "2_2") (pintype "passive"))
      (node (ref "C42") (pin "2") (pinfunction "2_2") (pintype "passive"))
      (node (ref "C5") (pin "2") (pinfunction "2_2") (pintype "passive"))
      (node (ref "C6") (pin "2") (pinfunction "2_2") (pintype "passive"))
      (node (ref "C9") (pin "2") (pinfunction "2_2") (pintype "passive"))
      (node (ref "J5") (pin "C1") (pinfunction "VSS_C1") (pintype "bidirectional"))
      (node (ref "J5") (pin "C2") (pinfunction "VSS_C2") (pintype "bidirectional"))
      (node (ref "J5") (pin "C3") (pinfunction "VSS_C3") (pintype "bidirectional"))
      (node (ref "J5") (pin "C4") (pinfunction "VSS_C4") (pintype "bidirectional"))
      (node (ref "J5") (pin "DSW2") (pinfunction "SW2_DSW2") (pintype "bidirectional"))
      (node (ref "J5") (pin "P6") (pinfunction "VSS_P6") (pintype "bidirectional"))
      (node (ref "JP1") (pin "6") (pinfunction "6_6") (pintype "passive"))
      (node (ref "JP3") (pin "1") (pinfunction "1_1") (pintype "passive"))
      (node (ref "R19") (pin "1") (pinfunction "1_1") (pintype "passive"))
      (node (ref "R28") (pin "2") (pinfunction "2_2") (pintype "passive"))
      (node (ref "R31") (pin "2") (pinfunction "2_2") (pintype "passive"))
      (node (ref "R8") (pin "1") (pinfunction "1_1") (pintype "passive"))
      (node (ref "SW1") (pin "S1") (pinfunction "1_S1") (pintype "passive"))
      (node (ref "SW2") (pin "1") (pinfunction "1_1") (pintype "passive"))
      (node (ref "SW2") (pin "2") (pinfunction "2_2") (pintype "passive"))
      (node (ref "SW2") (pin "3") (pinfunction "3_3") (pintype "passive"))
      (node (ref "SW2") (pin "4") (pinfunction "4_4") (pintype "passive"))
      (node (ref "U1") (pin "4") (pinfunction "GND_4") (pintype "bidirectional"))
      (node (ref "U2") (pin "4") (pinfunction "GND_4") (pintype "bidirectional"))
      (node (ref "U3") (pin "4") (pinfunction "GND_4") (pintype "bidirectional"))
      (node (ref "U5") (pin "4") (pinfunction "GND_4") (pintype "bidirectional"))
      (node (ref "U7") (pin "13") (pinfunction "GND_13") (pintype "power_in"))
      (node (ref "U7") (pin "18") (pinfunction "GND_18") (pintype "power_in"))
      (node (ref "U7") (pin "23") (pinfunction "GND_23") (pintype "power_in"))
      (node (ref "U7") (pin "28") (pinfunction "GND_28") (pintype "power_in"))
      (node (ref "U7") (pin "3") (pinfunction "GND_3") (pintype "power_in"))
      (node (ref "U7") (pin "33") (pinfunction "GND_33") (pintype "power_in"))
      (node (ref "U7") (pin "38") (pinfunction "GND_38") (pintype "power_in"))
      (node (ref "U7") (pin "8") (pinfunction "GND_8") (pintype "power_in"))
    )
    (net (code "28") (name "GP0_SD_MISO") (class "Default")
      (node (ref "R10") (pin "2") (pinfunction "2_2") (pintype "passive"))
      (node (ref "U7") (pin "1") (pinfunction "GP0_1") (pintype "bidirectional"))
    )
    (net (code "29") (name "GP1_SD_SS") (class "Default")
      (node (ref "R1") (pin "2") (pinfunction "2_2") (pintype "passive"))
      (node (ref "U7") (pin "2") (pinfunction "GP1_2") (pintype "bidirectional"))
    )
    (net (code "30") (name "GP2_SD_CLK") (class "Default")
      (node (ref "R4") (pin "2") (pinfunction "2_2") (pintype "passive"))
      (node (ref "U7") (pin "4") (pinfunction "GP2_4") (pintype "bidirectional"))
    )
    (net (code "31") (name "GP3_SD_MOSI") (class "Default")
      (node (ref "R2") (pin "2") (pinfunction "2_2") (pintype "passive"))
      (node (ref "U7") (pin "5") (pinfunction "GP3_5") (pintype "bidirectional"))
    )
    (net (code "32") (name "GP4_REBOOT") (class "Default")
      (node (ref "R27") (pin "1") (pinfunction "1_1") (pintype "passive"))
      (node (ref "U7") (pin "6") (pinfunction "GP4_6") (pintype "bidirectional"))
    )
    (net (code "33") (name "GP5_SD_DET") (class "Default")
      (node (ref "J5") (pin "DSW1") (pinfunction "SW1_DSW1") (pintype "bidirectional"))
      (node (ref "R3") (pin "2") (pinfunction "2_2") (pintype "passive"))
      (node (ref "U7") (pin "7") (pinfunction "GP5_7") (pintype "bidirectional"))
    )
    (net (code "34") (name "GP6_OLED_SDA") (class "Default")
      (node (ref "JP3") (pin "4") (pinfunction "4_4") (pintype "passive"))
      (node (ref "R15") (pin "2") (pinfunction "2_2") (pintype "passive"))
      (node (ref "U7") (pin "9") (pinfunction "GP6_9") (pintype "bidirectional"))
    )
    (net (code "35") (name "GP7_OLED_SCL") (class "Default")
      (node (ref "JP3") (pin "3") (pinfunction "3_3") (pintype "passive"))
      (node (ref "R9") (pin "2") (pinfunction "2_2") (pintype "passive"))
      (node (ref "U7") (pin "10") (pinfunction "GP7_10") (pintype "bidirectional"))
    )
    (net (code "36") (name "GP8_REVISION_1") (class "Default")
      (node (ref "R31") (pin "1") (pinfunction "1_1") (pintype "passive"))
      (node (ref "R35") (pin "2") (pinfunction "2_2") (pintype "passive"))
      (node (ref "U7") (pin "11") (pinfunction "GP8_11") (pintype "bidirectional"))
    )
    (net (code "37") (name "GP9") (class "Default")
      (node (ref "JP1") (pin "2") (pinfunction "2_2") (pintype "passive"))
      (node (ref "U7") (pin "12") (pinfunction "GP9_12") (pintype "bidirectional"))
    )
    (net (code "38") (name "GP10") (class "Default")
      (node (ref "JP1") (pin "1") (pinfunction "1_1") (pintype "passive"))
      (node (ref "U7") (pin "14") (pinfunction "GP10_14") (pintype "bidirectional"))
    )
    (net (code "39") (name "GP11") (class "Default")
      (node (ref "JP1") (pin "4") (pinfunction "4_4") (pintype "passive"))
      (node (ref "U7") (pin "15") (pinfunction "GP11_15") (pintype "bidirectional"))
    )
    (net (code "40") (name "GP12") (class "Default")
      (node (ref "JP1") (pin "3") (pinfunction "3_3") (pintype "passive"))
      (node (ref "U7") (pin "16") (pinfunction "GP12_16") (pintype "bidirectional"))
    )
    (net (code "41") (name "GP13") (class "Default")
      (node (ref "SW2") (pin "7") (pinfunction "7_7") (pintype "passive"))
      (node (ref "U7") (pin "17") (pinfunction "GP13_17") (pintype "bidirectional"))
    )
    (net (code "42") (name "GP14") (class "Default")
      (node (ref "SW2") (pin "6") (pinfunction "6_6") (pintype "passive"))
      (node (ref "U7") (pin "19") (pinfunction "GP14_19") (pintype "bidirectional"))
    )
    (net (code "43") (name "GP15") (class "Default")
      (node (ref "SW2") (pin "5") (pinfunction "5_5") (pintype "passive"))
      (node (ref "U7") (pin "20") (pinfunction "GP15_20") (pintype "bidirectional"))
    )
    (net (code "44") (name "GP22_REVISION_2") (class "Default")
      (node (ref "R28") (pin "1") (pinfunction "1_1") (pintype "passive"))
      (node (ref "R30") (pin "2") (pinfunction "2_2") (pintype "passive"))
      (node (ref "U7") (pin "29") (pinfunction "GP22_29") (pintype "bidirectional"))
    )
    (net (code "45") (name "GP28") (class "Default")
      (node (ref "SW2") (pin "8") (pinfunction "8_8") (pintype "passive"))
      (node (ref "U7") (pin "34") (pinfunction "GP28_34") (pintype "bidirectional"))
    )
    (net (code "46") (name "Net-(C8-Pad1)") (class "Default")
      (node (ref "C8") (pin "1") (pinfunction "1_1") (pintype "passive"))
      (node (ref "R11") (pin "2") (pinfunction "2_2") (pintype "passive"))
      (node (ref "R12") (pin "2") (pinfunction "2_2") (pintype "passive"))
      (node (ref "T1") (pin "6") (pinfunction "6_6") (pintype "bidirectional"))
    )
    (net (code "47") (name "Net-(C8-Pad2)") (class "Default")
      (node (ref "C8") (pin "2") (pinfunction "2_2") (pintype "passive"))
      (node (ref "R11") (pin "1") (pinfunction "1_1") (pintype "passive"))
      (node (ref "R13") (pin "2") (pinfunction "2_2") (pintype "passive"))
      (node (ref "T1") (pin "4") (pinfunction "4_4") (pintype "bidirectional"))
    )
    (net (code "48") (name "Net-(C23-Pad1)") (class "Default")
      (node (ref "C23") (pin "1") (pinfunction "1_1") (pintype "passive"))
      (node (ref "R36") (pin "2") (pinfunction "2_2") (pintype "passive"))
      (node (ref "R37") (pin "2") (pinfunction "2_2") (pintype "passive"))
      (node (ref "T3") (pin "6") (pinfunction "6_6") (pintype "bidirectional"))
    )
    (net (code "49") (name "Net-(C23-Pad2)") (class "Default")
      (node (ref "C23") (pin "2") (pinfunction "2_2") (pintype "passive"))
      (node (ref "R36") (pin "1") (pinfunction "1_1") (pintype "passive"))
      (node (ref "R38") (pin "2") (pinfunction "2_2") (pintype "passive"))
      (node (ref "T3") (pin "4") (pinfunction "4_4") (pintype "bidirectional"))
    )
    (net (code "50") (name "Net-(C30-Pad1)") (class "Default")
      (node (ref "C30") (pin "1") (pinfunction "1_1") (pintype "passive"))
      (node (ref "R46") (pin "2") (pinfunction "2_2") (pintype "passive"))
      (node (ref "R47") (pin "2") (pinfunction "2_2") (pintype "passive"))
      (node (ref "T7") (pin "6") (pinfunction "6_6") (pintype "bidirectional"))
    )
    (net (code "51") (name "Net-(C30-Pad2)") (class "Default")
      (node (ref "C30") (pin "2") (pinfunction "2_2") (pintype "passive"))
      (node (ref "R46") (pin "1") (pinfunction "1_1") (pintype "passive"))
      (node (ref "R48") (pin "2") (pinfunction "2_2") (pintype "passive"))
      (node (ref "T7") (pin "4") (pinfunction "4_4") (pintype "bidirectional"))
    )
    (net (code "52") (name "Net-(C37-Pad1)") (class "Default")
      (node (ref "C37") (pin "1") (pinfunction "1_1") (pintype "passive"))
      (node (ref "R56") (pin "2") (pinfunction "2_2") (pintype "passive"))
      (node (ref "R57") (pin "2") (pinfunction "2_2") (pintype "passive"))
      (node (ref "T5") (pin "6") (pinfunction "6_6") (pintype "bidirectional"))
    )
    (net (code "53") (name "Net-(C37-Pad2)") (class "Default")
      (node (ref "C37") (pin "2") (pinfunction "2_2") (pintype "passive"))
      (node (ref "R56") (pin "1") (pinfunction "1_1") (pintype "passive"))
      (node (ref "R58") (pin "2") (pinfunction "2_2") (pintype "passive"))
      (node (ref "T5") (pin "4") (pinfunction "4_4") (pintype "bidirectional"))
    )
    (net (code "54") (name "Net-(C40-Pad1)") (class "Default")
      (node (ref "C40") (pin "1") (pinfunction "1_1") (pintype "passive"))
      (node (ref "R29") (pin "1") (pinfunction "1_1") (pintype "passive"))
    )
    (net (code "55") (name "Net-(D3-K)") (class "Default")
      (node (ref "C10") (pin "1") (pinfunction "1_1") (pintype "passive"))
      (node (ref "D3") (pin "C") (pinfunction "K_C") (pintype "bidirectional"))
      (node (ref "L1") (pin "1") (pinfunction "P$1_1") (pintype "bidirectional"))
      (node (ref "R5") (pin "2") (pinfunction "2_2") (pintype "passive"))
      (node (ref "T1") (pin "1") (pinfunction "1_1") (pintype "bidirectional"))
    )
    (net (code "56") (name "Net-(D4-K)") (class "Default")
      (node (ref "C4") (pin "1") (pinfunction "1_1") (pintype "passive"))
      (node (ref "D4") (pin "C") (pinfunction "K_C") (pintype "bidirectional"))
      (node (ref "L3") (pin "1") (pinfunction "P$1_1") (pintype "bidirectional"))
      (node (ref "R6") (pin "2") (pinfunction "2_2") (pintype "passive"))
      (node (ref "T2") (pin "1") (pinfunction "1_1") (pintype "bidirectional"))
    )
    (net (code "57") (name "Net-(D8-K)") (class "Default")
      (node (ref "C18") (pin "1") (pinfunction "1_1") (pintype "passive"))
      (node (ref "D8") (pin "C") (pinfunction "K_C") (pintype "bidirectional"))
      (node (ref "L5") (pin "1") (pinfunction "P$1_1") (pintype "bidirectional"))
      (node (ref "R32") (pin "2") (pinfunction "2_2") (pintype "passive"))
      (node (ref "T3") (pin "1") (pinfunction "1_1") (pintype "bidirectional"))
    )
    (net (code "58") (name "Net-(D9-K)") (class "Default")
      (node (ref "C21") (pin "1") (pinfunction "1_1") (pintype "passive"))
      (node (ref "D9") (pin "C") (pinfunction "K_C") (pintype "bidirectional"))
      (node (ref "L7") (pin "1") (pinfunction "P$1_1") (pintype "bidirectional"))
      (node (ref "R33") (pin "2") (pinfunction "2_2") (pintype "passive"))
      (node (ref "T4") (pin "1") (pinfunction "1_1") (pintype "bidirectional"))
    )
    (net (code "59") (name "Net-(D10-K)") (class "Default")
      (node (ref "C25") (pin "1") (pinfunction "1_1") (pintype "passive"))
      (node (ref "D10") (pin "C") (pinfunction "K_C") (pintype "bidirectional"))
      (node (ref "L13") (pin "1") (pinfunction "P$1_1") (pintype "bidirectional"))
      (node (ref "R42") (pin "2") (pinfunction "2_2") (pintype "passive"))
      (node (ref "T7") (pin "1") (pinfunction "1_1") (pintype "bidirectional"))
    )
    (net (code "60") (name "Net-(D11-K)") (class "Default")
      (node (ref "C28") (pin "1") (pinfunction "1_1") (pintype "passive"))
      (node (ref "D11") (pin "C") (pinfunction "K_C") (pintype "bidirectional"))
      (node (ref "L15") (pin "1") (pinfunction "P$1_1") (pintype "bidirectional"))
      (node (ref "R43") (pin "2") (pinfunction "2_2") (pintype "passive"))
      (node (ref "T8") (pin "1") (pinfunction "1_1") (pintype "bidirectional"))
    )
    (net (code "61") (name "Net-(D12-K)") (class "Default")
      (node (ref "C32") (pin "1") (pinfunction "1_1") (pintype "passive"))
      (node (ref "D12") (pin "C") (pinfunction "K_C") (pintype "bidirectional"))
      (node (ref "L9") (pin "1") (pinfunction "P$1_1") (pintype "bidirectional"))
      (node (ref "R52") (pin "2") (pinfunction "2_2") (pintype "passive"))
      (node (ref "T5") (pin "1") (pinfunction "1_1") (pintype "bidirectional"))
    )
    (net (code "62") (name "Net-(D13-K)") (class "Default")
      (node (ref "C35") (pin "1") (pinfunction "1_1") (pintype "passive"))
      (node (ref "D13") (pin "C") (pinfunction "K_C") (pintype "bidirectional"))
      (node (ref "L11") (pin "1") (pinfunction "P$1_1") (pintype "bidirectional"))
      (node (ref "R53") (pin "2") (pinfunction "2_2") (pintype "passive"))
      (node (ref "T6") (pin "1") (pinfunction "1_1") (pintype "bidirectional"))
    )
    (net (code "63") (name "Net-(F1-P$1)") (class "Default")
      (node (ref "F1") (pin "1") (pinfunction "P$1_1") (pintype "bidirectional"))
      (node (ref "T1") (pin "2") (pinfunction "2_2") (pintype "bidirectional"))
    )
    (net (code "64") (name "Net-(F2-P$1)") (class "Default")
      (node (ref "F2") (pin "1") (pinfunction "P$1_1") (pintype "bidirectional"))
      (node (ref "T3") (pin "2") (pinfunction "2_2") (pintype "bidirectional"))
    )
    (net (code "65") (name "Net-(F3-P$1)") (class "Default")
      (node (ref "F3") (pin "1") (pinfunction "P$1_1") (pintype "bidirectional"))
      (node (ref "T5") (pin "2") (pinfunction "2_2") (pintype "bidirectional"))
    )
    (net (code "66") (name "Net-(F4-P$1)") (class "Default")
      (node (ref "F4") (pin "1") (pinfunction "P$1_1") (pintype "bidirectional"))
      (node (ref "T7") (pin "2") (pinfunction "2_2") (pintype "bidirectional"))
    )
    (net (code "67") (name "Net-(J4-V+)") (class "Default")
      (node (ref "CR1") (pin "A") (pinfunction "A_A") (pintype "bidirectional"))
      (node (ref "CR2") (pin "K") (pinfunction "K_K") (pintype "bidirectional"))
      (node (ref "J4") (pin "1") (pinfunction "V+_1") (pintype "bidirectional"))
    )
    (net (code "68") (name "Net-(J5-CLK)") (class "Default")
      (node (ref "J5") (pin "P5") (pinfunction "CLK_P5") (pintype "bidirectional"))
      (node (ref "R4") (pin "1") (pinfunction "1_1") (pintype "passive"))
    )
    (net (code "69") (name "Net-(J5-CMD{slash}MOSI)") (class "Default")
      (node (ref "J5") (pin "P3") (pinfunction "CMD/MOSI_P3") (pintype "bidirectional"))
      (node (ref "R2") (pin "1") (pinfunction "1_1") (pintype "passive"))
    )
    (net (code "70") (name "Net-(J5-DAT0{slash}MISO)") (class "Default")
      (node (ref "J5") (pin "P7") (pinfunction "DAT0/MISO_P7") (pintype "bidirectional"))
      (node (ref "R10") (pin "1") (pinfunction "1_1") (pintype "passive"))
    )
    (net (code "71") (name "Net-(J5-DAT3{slash}CS)") (class "Default")
      (node (ref "J5") (pin "P2") (pinfunction "DAT3/CS_P2") (pintype "bidirectional"))
      (node (ref "R1") (pin "1") (pinfunction "1_1") (pintype "passive"))
    )
    (net (code "72") (name "Net-(L2-P$1)") (class "Default")
      (node (ref "C2") (pin "2") (pinfunction "2_2") (pintype "passive"))
      (node (ref "D3") (pin "A") (pinfunction "A_A") (pintype "bidirectional"))
      (node (ref "L2") (pin "1") (pinfunction "P$1_1") (pintype "bidirectional"))
      (node (ref "R5") (pin "1") (pinfunction "1_1") (pintype "passive"))
      (node (ref "T1") (pin "3") (pinfunction "3_3") (pintype "bidirectional"))
    )
    (net (code "73") (name "Net-(L4-P$1)") (class "Default")
      (node (ref "C3") (pin "2") (pinfunction "2_2") (pintype "passive"))
      (node (ref "D4") (pin "A") (pinfunction "A_A") (pintype "bidirectional"))
      (node (ref "L4") (pin "1") (pinfunction "P$1_1") (pintype "bidirectional"))
      (node (ref "R6") (pin "1") (pinfunction "1_1") (pintype "passive"))
      (node (ref "T2") (pin "3") (pinfunction "3_3") (pintype "bidirectional"))
    )
    (net (code "74") (name "Net-(L6-P$1)") (class "Default")
      (node (ref "C19") (pin "2") (pinfunction "2_2") (pintype "passive"))
      (node (ref "D8") (pin "A") (pinfunction "A_A") (pintype "bidirectional"))
      (node (ref "L6") (pin "1") (pinfunction "P$1_1") (pintype "bidirectional"))
      (node (ref "R32") (pin "1") (pinfunction "1_1") (pintype "passive"))
      (node (ref "T3") (pin "3") (pinfunction "3_3") (pintype "bidirectional"))
    )
    (net (code "75") (name "Net-(L8-P$1)") (class "Default")
      (node (ref "C20") (pin "2") (pinfunction "2_2") (pintype "passive"))
      (node (ref "D9") (pin "A") (pinfunction "A_A") (pintype "bidirectional"))
      (node (ref "L8") (pin "1") (pinfunction "P$1_1") (pintype "bidirectional"))
      (node (ref "R33") (pin "1") (pinfunction "1_1") (pintype "passive"))
      (node (ref "T4") (pin "3") (pinfunction "3_3") (pintype "bidirectional"))
    )
    (net (code "76") (name "Net-(L10-P$1)") (class "Default")
      (node (ref "C33") (pin "2") (pinfunction "2_2") (pintype "passive"))
      (node (ref "D12") (pin "A") (pinfunction "A_A") (pintype "bidirectional"))
      (node (ref "L10") (pin "1") (pinfunction "P$1_1") (pintype "bidirectional"))
      (node (ref "R52") (pin "1") (pinfunction "1_1") (pintype "passive"))
      (node (ref "T5") (pin "3") (pinfunction "3_3") (pintype "bidirectional"))
    )
    (net (code "77") (name "Net-(L12-P$1)") (class "Default")
      (node (ref "C34") (pin "2") (pinfunction "2_2") (pintype "passive"))
      (node (ref "D13") (pin "A") (pinfunction "A_A") (pintype "bidirectional"))
      (node (ref "L12") (pin "1") (pinfunction "P$1_1") (pintype "bidirectional"))
      (node (ref "R53") (pin "1") (pinfunction "1_1") (pintype "passive"))
      (node (ref "T6") (pin "3") (pinfunction "3_3") (pintype "bidirectional"))
    )
    (net (code "78") (name "Net-(L14-P$1)") (class "Default")
      (node (ref "C26") (pin "2") (pinfunction "2_2") (pintype "passive"))
      (node (ref "D10") (pin "A") (pinfunction "A_A") (pintype "bidirectional"))
      (node (ref "L14") (pin "1") (pinfunction "P$1_1") (pintype "bidirectional"))
      (node (ref "R42") (pin "1") (pinfunction "1_1") (pintype "passive"))
      (node (ref "T7") (pin "3") (pinfunction "3_3") (pintype "bidirectional"))
    )
    (net (code "79") (name "Net-(L16-P$1)") (class "Default")
      (node (ref "C27") (pin "2") (pinfunction "2_2") (pintype "passive"))
      (node (ref "D11") (pin "A") (pinfunction "A_A") (pintype "bidirectional"))
      (node (ref "L16") (pin "1") (pinfunction "P$1_1") (pintype "bidirectional"))
      (node (ref "R43") (pin "1") (pinfunction "1_1") (pintype "passive"))
      (node (ref "T8") (pin "3") (pinfunction "3_3") (pintype "bidirectional"))
    )
    (net (code "80") (name "Net-(R7-Pad2)") (class "Default")
      (node (ref "R7") (pin "2") (pinfunction "2_2") (pintype "passive"))
      (node (ref "T2") (pin "2") (pinfunction "2_2") (pintype "bidirectional"))
    )
    (net (code "81") (name "Net-(R34-Pad2)") (class "Default")
      (node (ref "R34") (pin "2") (pinfunction "2_2") (pintype "passive"))
      (node (ref "T4") (pin "2") (pinfunction "2_2") (pintype "bidirectional"))
    )
    (net (code "82") (name "Net-(R44-Pad2)") (class "Default")
      (node (ref "R44") (pin "2") (pinfunction "2_2") (pintype "passive"))
      (node (ref "T8") (pin "2") (pinfunction "2_2") (pintype "bidirectional"))
    )
    (net (code "83") (name "Net-(R54-Pad2)") (class "Default")
      (node (ref "R54") (pin "2") (pinfunction "2_2") (pintype "passive"))
      (node (ref "T6") (pin "2") (pinfunction "2_2") (pintype "bidirectional"))
    )
    (net (code "84") (name "Net-(SW1-2)") (class "Default")
      (node (ref "R16") (pin "2") (pinfunction "2_2") (pintype "passive"))
      (node (ref "R27") (pin "2") (pinfunction "2_2") (pintype "passive"))
      (node (ref "SW1") (pin "S2") (pinfunction "2_S2") (pintype "passive"))
    )
    (net (code "85") (name "Net-(U1-A)") (class "Default")
      (node (ref "C22") (pin "2") (pinfunction "2_2") (pintype "passive"))
      (node (ref "R41") (pin "1") (pinfunction "1_1") (pintype "passive"))
      (node (ref "T4") (pin "4") (pinfunction "4_4") (pintype "bidirectional"))
      (node (ref "U1") (pin "8") (pinfunction "A_8") (pintype "bidirectional"))
    )
    (net (code "86") (name "Net-(U1-B)") (class "Default")
      (node (ref "C22") (pin "1") (pinfunction "1_1") (pintype "passive"))
      (node (ref "R41") (pin "2") (pinfunction "2_2") (pintype "passive"))
      (node (ref "T4") (pin "6") (pinfunction "6_6") (pintype "bidirectional"))
      (node (ref "U1") (pin "7") (pinfunction "B_7") (pintype "bidirectional"))
    )
    (net (code "87") (name "Net-(U1-Y)") (class "Default")
      (node (ref "R37") (pin "1") (pinfunction "1_1") (pintype "passive"))
      (node (ref "U1") (pin "5") (pinfunction "Y_5") (pintype "bidirectional"))
    )
    (net (code "88") (name "Net-(U1-Z)") (class "Default")
      (node (ref "R38") (pin "1") (pinfunction "1_1") (pintype "passive"))
      (node (ref "U1") (pin "6") (pinfunction "Z_6") (pintype "bidirectional"))
    )
    (net (code "89") (name "Net-(U2-A)") (class "Default")
      (node (ref "C36") (pin "2") (pinfunction "2_2") (pintype "passive"))
      (node (ref "R61") (pin "1") (pinfunction "1_1") (pintype "passive"))
      (node (ref "T6") (pin "4") (pinfunction "4_4") (pintype "bidirectional"))
      (node (ref "U2") (pin "8") (pinfunction "A_8") (pintype "bidirectional"))
    )
    (net (code "90") (name "Net-(U2-B)") (class "Default")
      (node (ref "C36") (pin "1") (pinfunction "1_1") (pintype "passive"))
      (node (ref "R61") (pin "2") (pinfunction "2_2") (pintype "passive"))
      (node (ref "T6") (pin "6") (pinfunction "6_6") (pintype "bidirectional"))
      (node (ref "U2") (pin "7") (pinfunction "B_7") (pintype "bidirectional"))
    )
    (net (code "91") (name "Net-(U2-Y)") (class "Default")
      (node (ref "R57") (pin "1") (pinfunction "1_1") (pintype "passive"))
      (node (ref "U2") (pin "5") (pinfunction "Y_5") (pintype "bidirectional"))
    )
    (net (code "92") (name "Net-(U2-Z)") (class "Default")
      (node (ref "R58") (pin "1") (pinfunction "1_1") (pintype "passive"))
      (node (ref "U2") (pin "6") (pinfunction "Z_6") (pintype "bidirectional"))
    )
    (net (code "93") (name "Net-(U3-A)") (class "Default")
      (node (ref "C7") (pin "2") (pinfunction "2_2") (pintype "passive"))
      (node (ref "R14") (pin "1") (pinfunction "1_1") (pintype "passive"))
      (node (ref "T2") (pin "4") (pinfunction "4_4") (pintype "bidirectional"))
      (node (ref "U3") (pin "8") (pinfunction "A_8") (pintype "bidirectional"))
    )
    (net (code "94") (name "Net-(U3-B)") (class "Default")
      (node (ref "C7") (pin "1") (pinfunction "1_1") (pintype "passive"))
      (node (ref "R14") (pin "2") (pinfunction "2_2") (pintype "passive"))
      (node (ref "T2") (pin "6") (pinfunction "6_6") (pintype "bidirectional"))
      (node (ref "U3") (pin "7") (pinfunction "B_7") (pintype "bidirectional"))
    )
    (net (code "95") (name "Net-(U3-Y)") (class "Default")
      (node (ref "R12") (pin "1") (pinfunction "1_1") (pintype "passive"))
      (node (ref "U3") (pin "5") (pinfunction "Y_5") (pintype "bidirectional"))
    )
    (net (code "96") (name "Net-(U3-Z)") (class "Default")
      (node (ref "R13") (pin "1") (pinfunction "1_1") (pintype "passive"))
      (node (ref "U3") (pin "6") (pinfunction "Z_6") (pintype "bidirectional"))
    )
    (net (code "97") (name "Net-(U5-A)") (class "Default")
      (node (ref "C29") (pin "2") (pinfunction "2_2") (pintype "passive"))
      (node (ref "R51") (pin "1") (pinfunction "1_1") (pintype "passive"))
      (node (ref "T8") (pin "4") (pinfunction "4_4") (pintype "bidirectional"))
      (node (ref "U5") (pin "8") (pinfunction "A_8") (pintype "bidirectional"))
    )
    (net (code "98") (name "Net-(U5-B)") (class "Default")
      (node (ref "C29") (pin "1") (pinfunction "1_1") (pintype "passive"))
      (node (ref "R51") (pin "2") (pinfunction "2_2") (pintype "passive"))
      (node (ref "T8") (pin "6") (pinfunction "6_6") (pintype "bidirectional"))
      (node (ref "U5") (pin "7") (pinfunction "B_7") (pintype "bidirectional"))
    )
    (net (code "99") (name "Net-(U5-Y)") (class "Default")
      (node (ref "R47") (pin "1") (pinfunction "1_1") (pintype "passive"))
      (node (ref "U5") (pin "5") (pinfunction "Y_5") (pintype "bidirectional"))
    )
    (net (code "100") (name "Net-(U5-Z)") (class "Default")
      (node (ref "R48") (pin "1") (pinfunction "1_1") (pintype "passive"))
      (node (ref "U5") (pin "6") (pinfunction "Z_6") (pintype "bidirectional"))
    )
    (net (code "101") (name "Net-(U7-GP16)") (class "Default")
      (node (ref "R24") (pin "2") (pinfunction "2_2") (pintype "passive"))
      (node (ref "U7") (pin "21") (pinfunction "GP16_21") (pintype "bidirectional"))
    )
    (net (code "102") (name "Net-(U7-GP17)") (class "Default")
      (node (ref "R23") (pin "2") (pinfunction "2_2") (pintype "passive"))
      (node (ref "U7") (pin "22") (pinfunction "GP17_22") (pintype "bidirectional"))
    )
    (net (code "103") (name "Net-(U7-GP18)") (class "Default")
      (node (ref "R25") (pin "2") (pinfunction "2_2") (pintype "passive"))
      (node (ref "U7") (pin "24") (pinfunction "GP18_24") (pintype "bidirectional"))
    )
    (net (code "104") (name "Net-(U7-GP19)") (class "Default")
      (node (ref "R22") (pin "2") (pinfunction "2_2") (pintype "passive"))
      (node (ref "U7") (pin "25") (pinfunction "GP19_25") (pintype "bidirectional"))
    )
    (net (code "105") (name "Net-(U7-GP20)") (class "Default")
      (node (ref "R26") (pin "2") (pinfunction "2_2") (pintype "passive"))
      (node (ref "U7") (pin "26") (pinfunction "GP20_26") (pintype "bidirectional"))
    )
    (net (code "106") (name "Net-(U7-GP21)") (class "Default")
      (node (ref "R21") (pin "2") (pinfunction "2_2") (pintype "passive"))
      (node (ref "U7") (pin "27") (pinfunction "GP21_27") (pintype "bidirectional"))
    )
    (net (code "107") (name "Net-(U7-GP26)") (class "Default")
      (node (ref "R20") (pin "2") (pinfunction "2_2") (pintype "passive"))
      (node (ref "U7") (pin "31") (pinfunction "GP26_31") (pintype "bidirectional"))
    )
    (net (code "108") (name "Net-(U7-GP27)") (class "Default")
      (node (ref "R17") (pin "2") (pinfunction "2_2") (pintype "passive"))
      (node (ref "U7") (pin "32") (pinfunction "GP27_32") (pintype "bidirectional"))
    )
    (net (code "109") (name "PE") (class "Default")
      (node (ref "C10") (pin "2") (pinfunction "2_2") (pintype "passive"))
      (node (ref "C16") (pin "2") (pinfunction "2_2") (pintype "passive"))
      (node (ref "C18") (pin "2") (pinfunction "2_2") (pintype "passive"))
      (node (ref "C19") (pin "1") (pinfunction "1_1") (pintype "passive"))
      (node (ref "C2") (pin "1") (pinfunction "1_1") (pintype "passive"))
      (node (ref "C20") (pin "1") (pinfunction "1_1") (pintype "passive"))
      (node (ref "C21") (pin "2") (pinfunction "2_2") (pintype "passive"))
      (node (ref "C25") (pin "2") (pinfunction "2_2") (pintype "passive"))
      (node (ref "C26") (pin "1") (pinfunction "1_1") (pintype "passive"))
      (node (ref "C27") (pin "1") (pinfunction "1_1") (pintype "passive"))
      (node (ref "C28") (pin "2") (pinfunction "2_2") (pintype "passive"))
      (node (ref "C3") (pin "1") (pinfunction "1_1") (pintype "passive"))
      (node (ref "C32") (pin "2") (pinfunction "2_2") (pintype "passive"))
      (node (ref "C33") (pin "1") (pinfunction "1_1") (pintype "passive"))
      (node (ref "C34") (pin "1") (pinfunction "1_1") (pintype "passive"))
      (node (ref "C35") (pin "2") (pinfunction "2_2") (pintype "passive"))
      (node (ref "C38") (pin "2") (pinfunction "2_2") (pintype "passive"))
      (node (ref "C39") (pin "2") (pinfunction "2_2") (pintype "passive"))
      (node (ref "C4") (pin "2") (pinfunction "2_2") (pintype "passive"))
      (node (ref "C40") (pin "2") (pinfunction "2_2") (pintype "passive"))
      (node (ref "CR2") (pin "A") (pinfunction "A_A") (pintype "bidirectional"))
      (node (ref "GDT1") (pin "C") (pinfunction "C_C") (pintype "bidirectional"))
      (node (ref "GDT2") (pin "C") (pinfunction "C_C") (pintype "bidirectional"))
      (node (ref "GDT3") (pin "C") (pinfunction "C_C") (pintype "bidirectional"))
      (node (ref "GDT4") (pin "C") (pinfunction "C_C") (pintype "bidirectional"))
      (node (ref "GDT5") (pin "C") (pinfunction "C_C") (pintype "bidirectional"))
      (node (ref "GDT6") (pin "C") (pinfunction "C_C") (pintype "bidirectional"))
      (node (ref "GDT7") (pin "C") (pinfunction "C_C") (pintype "bidirectional"))
      (node (ref "GDT8") (pin "C") (pinfunction "C_C") (pintype "bidirectional"))
      (node (ref "J1") (pin "S1") (pinfunction "S1_S1") (pintype "bidirectional"))
      (node (ref "J1") (pin "S2") (pinfunction "S2_S2") (pintype "bidirectional"))
      (node (ref "J2") (pin "S1") (pinfunction "S1_S1") (pintype "bidirectional"))
      (node (ref "J2") (pin "S2") (pinfunction "S2_S2") (pintype "bidirectional"))
      (node (ref "J3") (pin "P$1") (pinfunction "P$1_P$1") (pintype "bidirectional"))
      (node (ref "J3") (pin "P$2") (pinfunction "P$2_P$2") (pintype "bidirectional"))
      (node (ref "J3") (pin "P$3") (pinfunction "P$3_P$3") (pintype "bidirectional"))
      (node (ref "J3") (pin "P$4") (pinfunction "P$4_P$4") (pintype "bidirectional"))
      (node (ref "J4") (pin "2") (pinfunction "GND_2") (pintype "bidirectional"))
      (node (ref "R34") (pin "1") (pinfunction "1_1") (pintype "passive"))
      (node (ref "R44") (pin "1") (pinfunction "1_1") (pintype "passive"))
      (node (ref "R54") (pin "1") (pinfunction "1_1") (pintype "passive"))
      (node (ref "R7") (pin "1") (pinfunction "1_1") (pintype "passive"))
      (node (ref "R8") (pin "2") (pinfunction "2_2") (pintype "passive"))
    )
    (net (code "110") (name "SWGND") (class "Default")
      (node (ref "U7") (pin "42") (pinfunction "SWGND_42") (pintype "power_in"))
    )
    (net (code "111") (name "V+") (class "Default")
      (node (ref "CR1") (pin "K") (pinfunction "K_K") (pintype "bidirectional"))
      (node (ref "F1") (pin "2") (pinfunction "P$2_2") (pintype "bidirectional"))
      (node (ref "F2") (pin "2") (pinfunction "P$2_2") (pintype "bidirectional"))
      (node (ref "F3") (pin "2") (pinfunction "P$2_2") (pintype "bidirectional"))
      (node (ref "F4") (pin "2") (pinfunction "P$2_2") (pintype "bidirectional"))
      (node (ref "R29") (pin "2") (pinfunction "2_2") (pintype "passive"))
    )
    (net (code "112") (name "VBUS") (class "Default")
      (node (ref "U7") (pin "40") (pinfunction "VBUS_40") (pintype "power_in"))
    )
    (net (code "113") (name "VMID") (class "Default")
      (node (ref "C1") (pin "1") (pinfunction "1_1") (pintype "passive"))
      (node (ref "C17") (pin "1") (pinfunction "1_1") (pintype "passive"))
      (node (ref "C24") (pin "1") (pinfunction "1_1") (pintype "passive"))
      (node (ref "C31") (pin "1") (pinfunction "1_1") (pintype "passive"))
      (node (ref "R18") (pin "1") (pinfunction "1_1") (pintype "passive"))
      (node (ref "R19") (pin "2") (pinfunction "2_2") (pintype "passive"))
      (node (ref "T2") (pin "5") (pinfunction "5_5") (pintype "bidirectional"))
      (node (ref "T4") (pin "5") (pinfunction "5_5") (pintype "bidirectional"))
      (node (ref "T6") (pin "5") (pinfunction "5_5") (pintype "bidirectional"))
      (node (ref "T8") (pin "5") (pinfunction "5_5") (pintype "bidirectional"))
    )
    (net (code "114") (name "VSYS") (class "Default")
      (node (ref "U7") (pin "39") (pinfunction "VSYS_39") (pintype "power_in"))
    )
    (net (code "115") (name "unconnected-(J4-NO-Pad3)") (class "Default")
      (node (ref "J4") (pin "3") (pinfunction "NO_3") (pintype "bidirectional"))
    )
    (net (code "116") (name "unconnected-(J5-DAT1-PadP8)") (class "Default")
      (node (ref "J5") (pin "P8") (pinfunction "DAT1_P8") (pintype "bidirectional"))
    )
    (net (code "117") (name "unconnected-(J5-DAT2-PadP1)") (class "Default")
      (node (ref "J5") (pin "P1") (pinfunction "DAT2_P1") (pintype "bidirectional"))
    )
    (net (code "118") (name "unconnected-(T1-Pad5)") (class "Default")
      (node (ref "T1") (pin "5") (pinfunction "5_5") (pintype "bidirectional"))
    )
    (net (code "119") (name "unconnected-(T3-Pad5)") (class "Default")
      (node (ref "T3") (pin "5") (pinfunction "5_5") (pintype "bidirectional"))
    )
    (net (code "120") (name "unconnected-(T5-Pad5)") (class "Default")
      (node (ref "T5") (pin "5") (pinfunction "5_5") (pintype "bidirectional"))
    )
    (net (code "121") (name "unconnected-(T7-Pad5)") (class "Default")
      (node (ref "T7") (pin "5") (pinfunction "5_5") (pintype "bidirectional"))
    )
    (net (code "122") (name "unconnected-(U7-3V3_EN-Pad37)") (class "Default")
      (node (ref "U7") (pin "37") (pinfunction "3V3_EN_37") (pintype "input"))
    )
    (net (code "123") (name "unconnected-(U7-ADC_REF-Pad35)") (class "Default")
      (node (ref "U7") (pin "35") (pinfunction "ADC_REF_35") (pintype "input"))
    )
    (net (code "124") (name "unconnected-(U7-RUN-Pad30)") (class "Default")
      (node (ref "U7") (pin "30") (pinfunction "RUN_30") (pintype "input"))
    )
    (net (code "125") (name "unconnected-(U7-SWCLK-Pad41)") (class "Default")
      (node (ref "U7") (pin "41") (pinfunction "SWCLK_41") (pintype "input"))
    )
    (net (code "126") (name "unconnected-(U7-SWDIO-Pad43)") (class "Default")
      (node (ref "U7") (pin "43") (pinfunction "SWDIO_43") (pintype "bidirectional"))
    )
  )
)
